# Sample_wiring.net
KiCad netlist of a schematic drawn in EAGLE
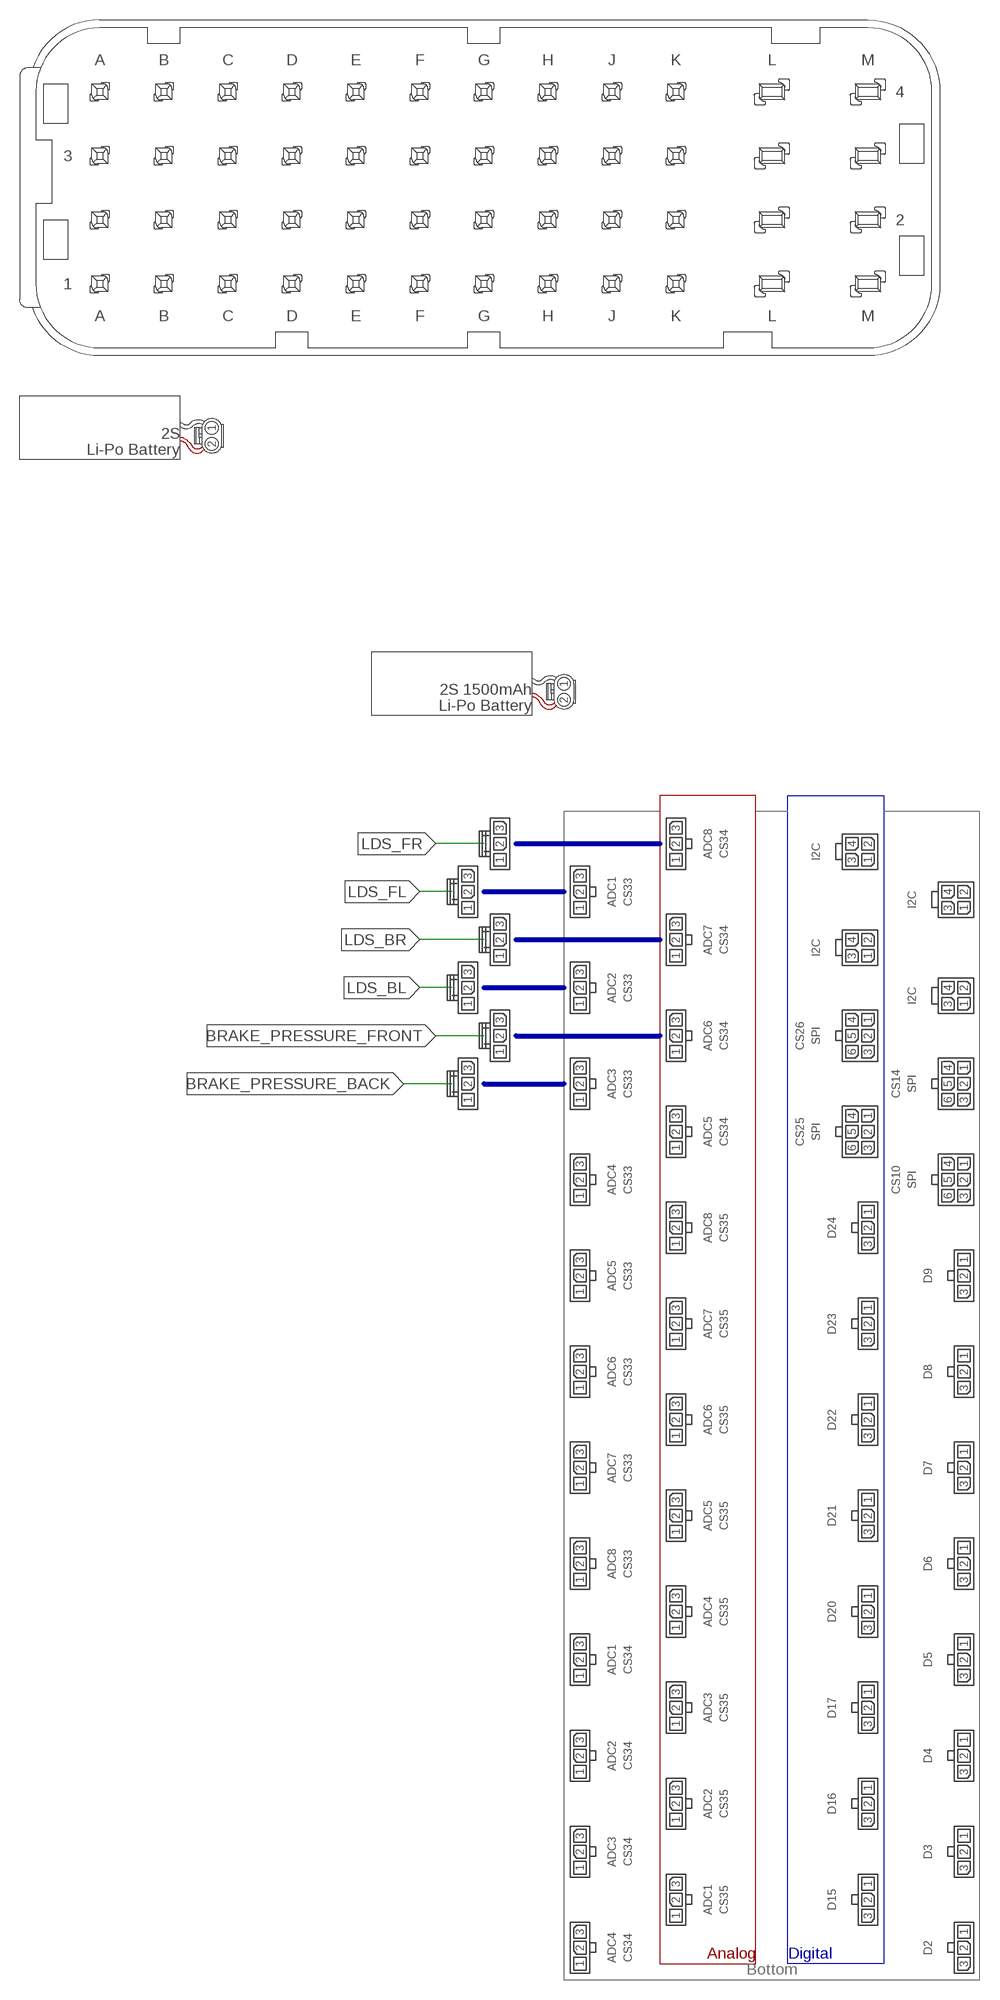
[diagram p0: schematic, sheet 1, part 1 of 2]
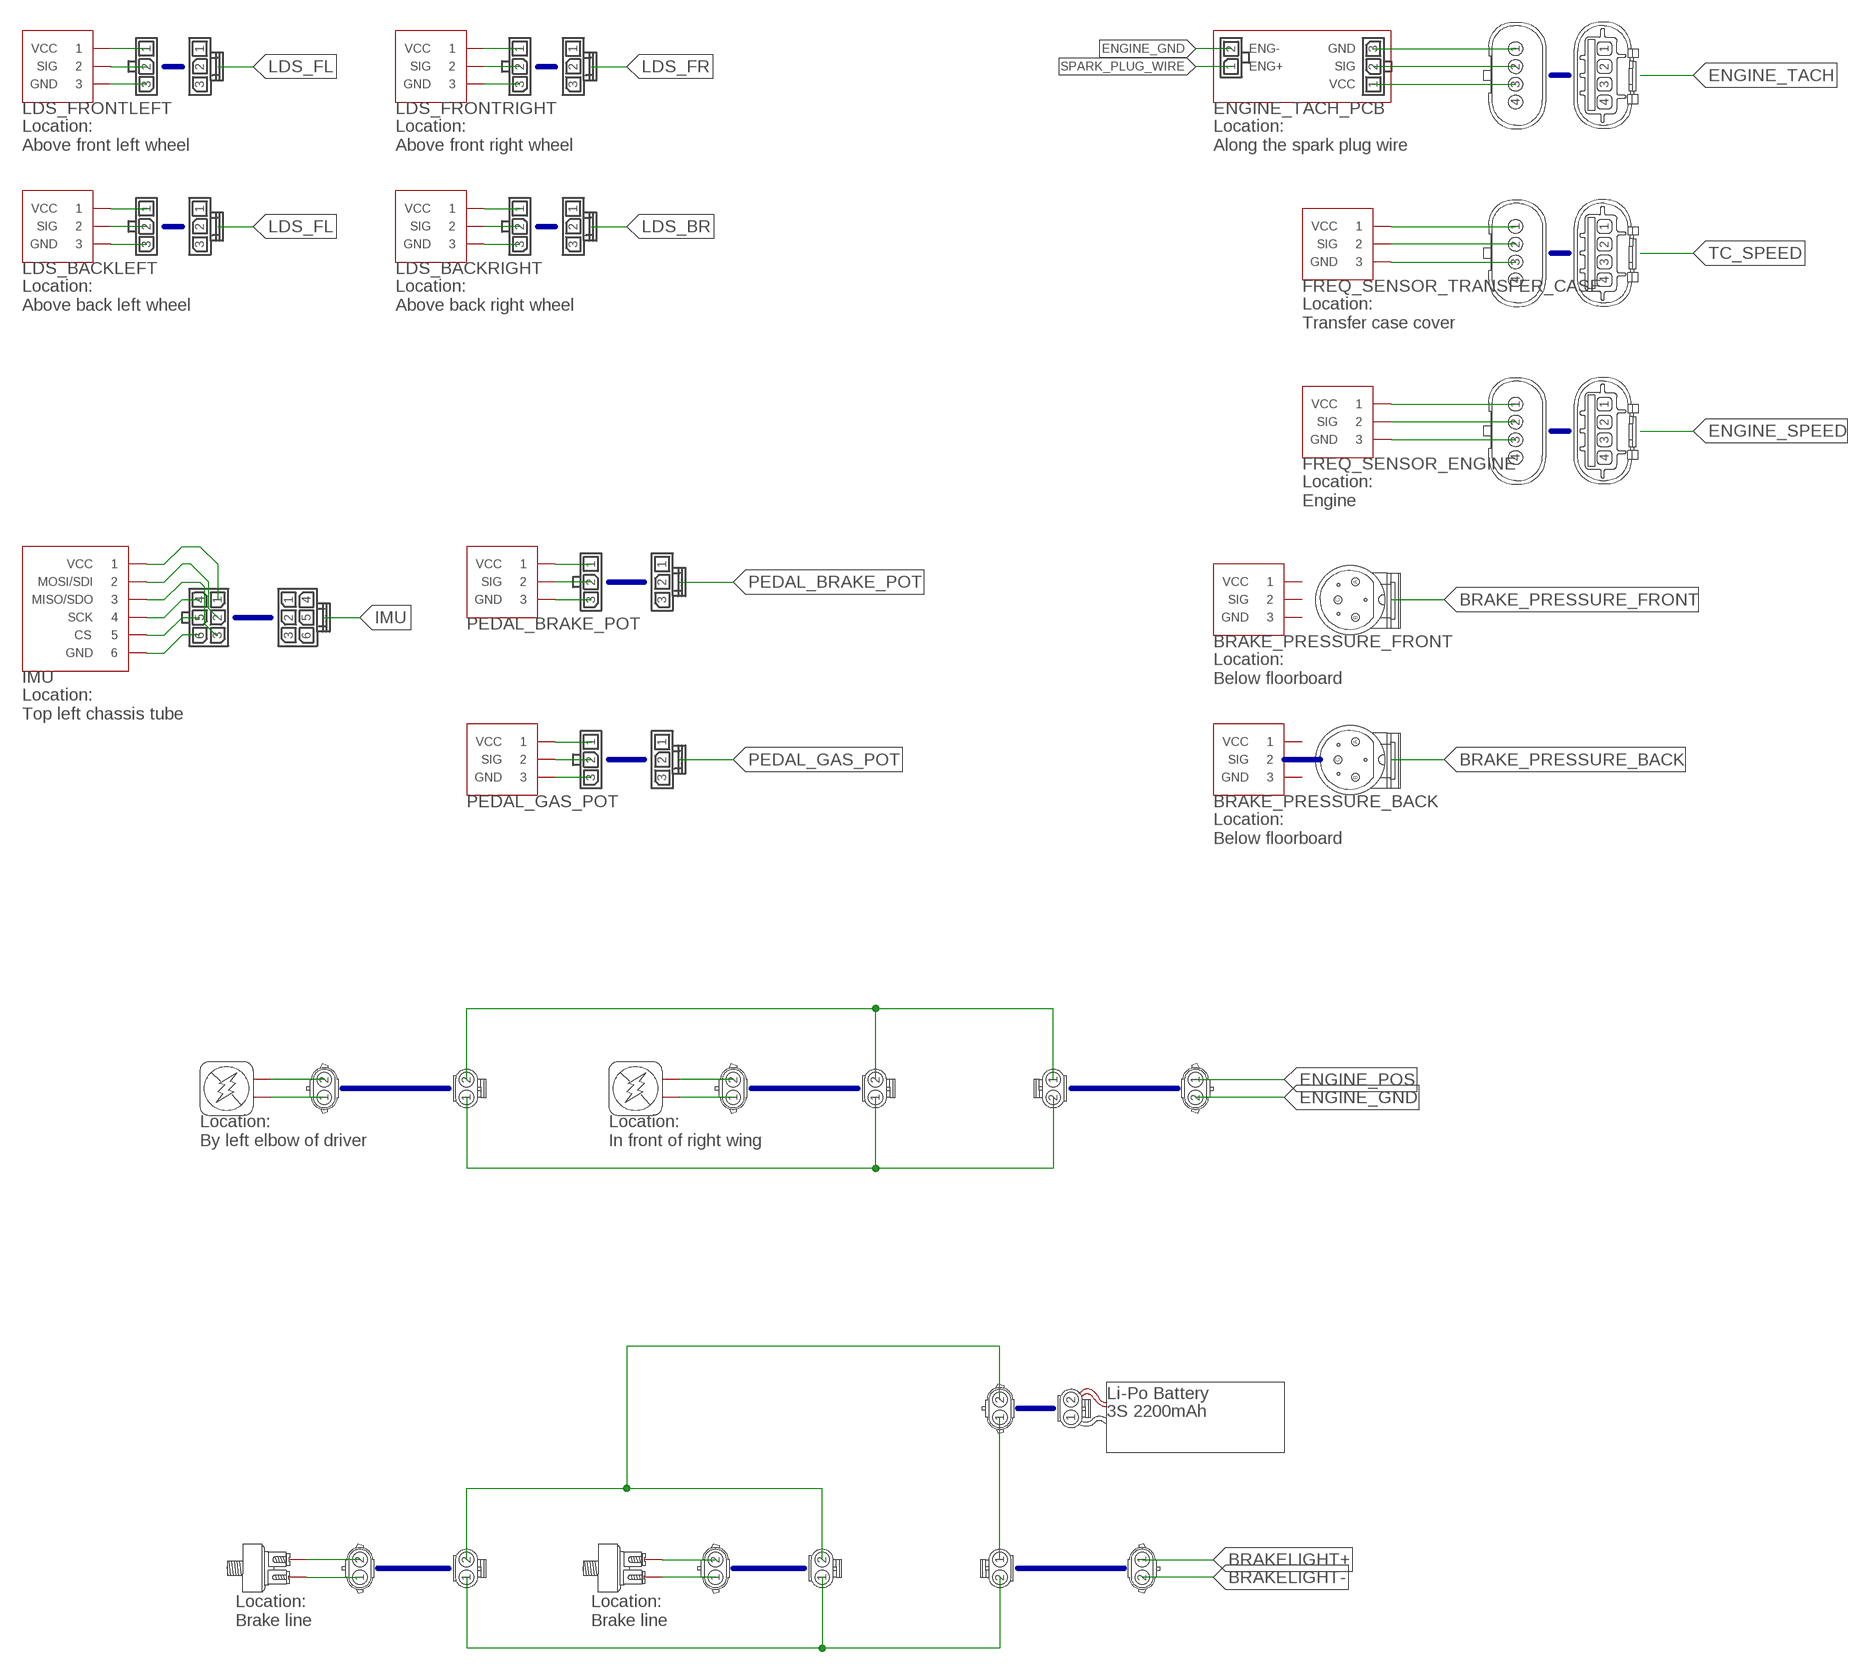
[diagram p1: schematic, sheet 1, part 2 of 2]

(export (version "E")
  (design (tool "Eeschema 10.0.6"))
  (components
    (comp (ref "BRAKE_PRESSURE_BACK")
      (value "SENSOR_1X3")
      (footprint "eagle-import:PINS_3")
      (libsource (lib "eagle-import") (part "SENSOR_1X3"))
    )
    (comp (ref "BRAKE_PRESSURE_FRONT")
      (value "SENSOR_1X3")
      (footprint "eagle-import:PINS_3")
      (libsource (lib "eagle-import") (part "SENSOR_1X3"))
    )
    (comp (ref "ENGINE_TACH_PCB")
      (value "ENGINE_TACH_PCB")
      (footprint "eagle-import:PINS_7")
      (libsource (lib "eagle-import") (part "ENGINE_TACH_PCB"))
    )
    (comp (ref "FREQ_SENSOR_ENGINE")
      (value "SENSOR_1X3")
      (footprint "eagle-import:PINS_3")
      (libsource (lib "eagle-import") (part "SENSOR_1X3"))
    )
    (comp (ref "FREQ_SENSOR_TRANSFER_CASE")
      (value "SENSOR_1X3")
      (footprint "eagle-import:PINS_3")
      (libsource (lib "eagle-import") (part "SENSOR_1X3"))
    )
    (comp (ref "IMU")
      (value "SENSOR_SPI_2X3")
      (footprint "eagle-import:PINS_7")
      (libsource (lib "eagle-import") (part "SENSOR_SPI_2X3"))
    )
    (comp (ref "LDS_BACKLEFT")
      (value "SENSOR_1X3")
      (footprint "eagle-import:PINS_3")
      (libsource (lib "eagle-import") (part "SENSOR_1X3"))
    )
    (comp (ref "LDS_BACKRIGHT")
      (value "SENSOR_1X3")
      (footprint "eagle-import:PINS_3")
      (libsource (lib "eagle-import") (part "SENSOR_1X3"))
    )
    (comp (ref "LDS_FRONTLEFT")
      (value "SENSOR_1X3")
      (footprint "eagle-import:PINS_3")
      (libsource (lib "eagle-import") (part "SENSOR_1X3"))
    )
    (comp (ref "LDS_FRONTRIGHT")
      (value "SENSOR_1X3")
      (footprint "eagle-import:PINS_3")
      (libsource (lib "eagle-import") (part "SENSOR_1X3"))
    )
    (comp (ref "PEDAL_BRAKE_POT")
      (value "SENSOR_1X3")
      (footprint "eagle-import:PINS_3")
      (libsource (lib "eagle-import") (part "SENSOR_1X3"))
    )
    (comp (ref "PEDAL_GAS_POT")
      (value "SENSOR_1X3")
      (footprint "eagle-import:PINS_3")
      (libsource (lib "eagle-import") (part "SENSOR_1X3"))
    )
    (comp (ref "U$1")
      (value "MICROFIT_1X3_MALE")
      (footprint "eagle-import:PINS_4")
      (libsource (lib "eagle-import") (part "MICROFIT_1X3_MALE"))
    )
    (comp (ref "U$2")
      (value "CMC_48PIN_PLUG_PCB")
      (footprint "eagle-import:PINS_49")
      (libsource (lib "eagle-import") (part "CMC_48PIN_PLUG_PCB"))
    )
    (comp (ref "U$3")
      (value "AUXDAQ_REV2")
      (footprint "eagle-import:PINS_200")
      (libsource (lib "eagle-import") (part "AUXDAQ_REV2"))
    )
    (comp (ref "U$4")
      (value "SKIDOO_KILLSWITCH")
      (footprint "eagle-import:PINS_3")
      (libsource (lib "eagle-import") (part "SKIDOO_KILLSWITCH"))
    )
    (comp (ref "U$5")
      (value "WEATHERPACK_1X2_MALE")
      (footprint "eagle-import:PINS_3")
      (libsource (lib "eagle-import") (part "WEATHERPACK_1X2_MALE"))
    )
    (comp (ref "U$6")
      (value "WEATHERPACK_1X2_FEMALE")
      (footprint "eagle-import:PINS_3")
      (libsource (lib "eagle-import") (part "WEATHERPACK_1X2_FEMALE"))
    )
    (comp (ref "U$7")
      (value "WEATHERPACK_1X2_MALE")
      (footprint "eagle-import:PINS_3")
      (libsource (lib "eagle-import") (part "WEATHERPACK_1X2_MALE"))
    )
    (comp (ref "U$8")
      (value "WEATHERPACK_1X2_MALE")
      (footprint "eagle-import:PINS_3")
      (libsource (lib "eagle-import") (part "WEATHERPACK_1X2_MALE"))
    )
    (comp (ref "U$9")
      (value "SKIDOO_KILLSWITCH")
      (footprint "eagle-import:PINS_3")
      (libsource (lib "eagle-import") (part "SKIDOO_KILLSWITCH"))
    )
    (comp (ref "U$10")
      (value "WEATHERPACK_1X2_FEMALE")
      (footprint "eagle-import:PINS_3")
      (libsource (lib "eagle-import") (part "WEATHERPACK_1X2_FEMALE"))
    )
    (comp (ref "U$11")
      (value "WEATHERPACK_1X2_FEMALE")
      (footprint "eagle-import:PINS_3")
      (libsource (lib "eagle-import") (part "WEATHERPACK_1X2_FEMALE"))
    )
    (comp (ref "U$12")
      (value "BRAKELIGHT_SWITCH_HYDRAULIC")
      (footprint "eagle-import:PINS_3")
      (libsource (lib "eagle-import") (part "BRAKELIGHT_SWITCH_HYDRAULIC"))
    )
    (comp (ref "U$13")
      (value "WEATHERPACK_1X2_MALE")
      (footprint "eagle-import:PINS_3")
      (libsource (lib "eagle-import") (part "WEATHERPACK_1X2_MALE"))
    )
    (comp (ref "U$14")
      (value "MICROFIT_1X3_MALE")
      (footprint "eagle-import:PINS_4")
      (libsource (lib "eagle-import") (part "MICROFIT_1X3_MALE"))
    )
    (comp (ref "U$15")
      (value "WEATHERPACK_1X2_FEMALE")
      (footprint "eagle-import:PINS_3")
      (libsource (lib "eagle-import") (part "WEATHERPACK_1X2_FEMALE"))
    )
    (comp (ref "U$16")
      (value "WEATHERPACK_1X2_MALE")
      (footprint "eagle-import:PINS_3")
      (libsource (lib "eagle-import") (part "WEATHERPACK_1X2_MALE"))
    )
    (comp (ref "U$17")
      (value "WEATHERPACK_1X2_MALE")
      (footprint "eagle-import:PINS_3")
      (libsource (lib "eagle-import") (part "WEATHERPACK_1X2_MALE"))
    )
    (comp (ref "U$18")
      (value "BRAKELIGHT_SWITCH_HYDRAULIC")
      (footprint "eagle-import:PINS_3")
      (libsource (lib "eagle-import") (part "BRAKELIGHT_SWITCH_HYDRAULIC"))
    )
    (comp (ref "U$19")
      (value "WEATHERPACK_1X2_FEMALE")
      (footprint "eagle-import:PINS_3")
      (libsource (lib "eagle-import") (part "WEATHERPACK_1X2_FEMALE"))
    )
    (comp (ref "U$20")
      (value "WEATHERPACK_1X2_FEMALE")
      (footprint "eagle-import:PINS_3")
      (libsource (lib "eagle-import") (part "WEATHERPACK_1X2_FEMALE"))
    )
    (comp (ref "U$21")
      (value "MICROFIT_1X3_MALE")
      (footprint "eagle-import:PINS_4")
      (libsource (lib "eagle-import") (part "MICROFIT_1X3_MALE"))
    )
    (comp (ref "U$22")
      (value "MICROFIT_1X3_MALE")
      (footprint "eagle-import:PINS_4")
      (libsource (lib "eagle-import") (part "MICROFIT_1X3_MALE"))
    )
    (comp (ref "U$23")
      (value "MICROFIT_2X3_MALE")
      (footprint "eagle-import:PINS_7")
      (libsource (lib "eagle-import") (part "MICROFIT_2X3_MALE"))
    )
    (comp (ref "U$24")
      (value "MICROFIT_1X3_MALE")
      (footprint "eagle-import:PINS_4")
      (libsource (lib "eagle-import") (part "MICROFIT_1X3_MALE"))
    )
    (comp (ref "U$25")
      (value "MICROFIT_1X3_MALE")
      (footprint "eagle-import:PINS_4")
      (libsource (lib "eagle-import") (part "MICROFIT_1X3_MALE"))
    )
    (comp (ref "U$26")
      (value "SQUBA_1X4_MALE")
      (footprint "eagle-import:PINS_5")
      (libsource (lib "eagle-import") (part "SQUBA_1X4_MALE"))
    )
    (comp (ref "U$27")
      (value "SQUBA_1X4_MALE")
      (footprint "eagle-import:PINS_5")
      (libsource (lib "eagle-import") (part "SQUBA_1X4_MALE"))
    )
    (comp (ref "U$28")
      (value "SQUBA_1X4_MALE")
      (footprint "eagle-import:PINS_5")
      (libsource (lib "eagle-import") (part "SQUBA_1X4_MALE"))
    )
    (comp (ref "U$29")
      (value "3S 2200mAh")
      (footprint "eagle-import:PINS_200")
      (libsource (lib "eagle-import") (part "LIPO_BATT"))
    )
    (comp (ref "U$30")
      (value "2S 1500mAh")
      (footprint "eagle-import:PINS_200")
      (libsource (lib "eagle-import") (part "LIPO_BATT"))
    )
    (comp (ref "U$31")
      (value "2S")
      (footprint "eagle-import:PINS_200")
      (libsource (lib "eagle-import") (part "LIPO_BATT"))
    )
    (comp (ref "U$32")
      (value "WEATHERPACK_1X2_MALE")
      (footprint "eagle-import:PINS_3")
      (libsource (lib "eagle-import") (part "WEATHERPACK_1X2_MALE"))
    )
    (comp (ref "U$33")
      (value "MICROFIT_2X3_FEMALE")
      (footprint "eagle-import:PINS_7")
      (libsource (lib "eagle-import") (part "MICROFIT_2X3_FEMALE"))
    )
    (comp (ref "U$34")
      (value "SQUBA_1X4_FEMALE")
      (footprint "eagle-import:PINS_5")
      (libsource (lib "eagle-import") (part "SQUBA_1X4_FEMALE"))
    )
    (comp (ref "U$35")
      (value "SQUBA_1X4_FEMALE")
      (footprint "eagle-import:PINS_5")
      (libsource (lib "eagle-import") (part "SQUBA_1X4_FEMALE"))
    )
    (comp (ref "U$36")
      (value "SQUBA_1X4_FEMALE")
      (footprint "eagle-import:PINS_5")
      (libsource (lib "eagle-import") (part "SQUBA_1X4_FEMALE"))
    )
    (comp (ref "U$37")
      (value "MICROFIT_1X3_FEMALE")
      (footprint "eagle-import:PINS_4")
      (libsource (lib "eagle-import") (part "MICROFIT_1X3_FEMALE"))
    )
    (comp (ref "U$38")
      (value "MICROFIT_1X3_FEMALE")
      (footprint "eagle-import:PINS_4")
      (libsource (lib "eagle-import") (part "MICROFIT_1X3_FEMALE"))
    )
    (comp (ref "U$39")
      (value "MICROFIT_1X3_FEMALE")
      (footprint "eagle-import:PINS_4")
      (libsource (lib "eagle-import") (part "MICROFIT_1X3_FEMALE"))
    )
    (comp (ref "U$40")
      (value "MICROFIT_1X3_FEMALE")
      (footprint "eagle-import:PINS_4")
      (libsource (lib "eagle-import") (part "MICROFIT_1X3_FEMALE"))
    )
    (comp (ref "U$41")
      (value "MICROFIT_1X3_FEMALE")
      (footprint "eagle-import:PINS_4")
      (libsource (lib "eagle-import") (part "MICROFIT_1X3_FEMALE"))
    )
    (comp (ref "U$42")
      (value "MICROFIT_1X3_FEMALE")
      (footprint "eagle-import:PINS_4")
      (libsource (lib "eagle-import") (part "MICROFIT_1X3_FEMALE"))
    )
    (comp (ref "U$43")
      (value "MICROFIT_1X3_FEMALE")
      (footprint "eagle-import:PINS_4")
      (libsource (lib "eagle-import") (part "MICROFIT_1X3_FEMALE"))
    )
    (comp (ref "U$44")
      (value "MICROFIT_1X3_FEMALE")
      (footprint "eagle-import:PINS_4")
      (libsource (lib "eagle-import") (part "MICROFIT_1X3_FEMALE"))
    )
    (comp (ref "U$45")
      (value "MICROFIT_1X3_FEMALE")
      (footprint "eagle-import:PINS_4")
      (libsource (lib "eagle-import") (part "MICROFIT_1X3_FEMALE"))
    )
    (comp (ref "U$46")
      (value "MICROFIT_1X3_FEMALE")
      (footprint "eagle-import:PINS_4")
      (libsource (lib "eagle-import") (part "MICROFIT_1X3_FEMALE"))
    )
    (comp (ref "U$47")
      (value "METRIPACK_3PIN_FEMALE")
      (footprint "eagle-import:PINS_3")
      (libsource (lib "eagle-import") (part "METRIPACK_3PIN_FEMALE"))
    )
    (comp (ref "U$48")
      (value "METRIPACK_3PIN_FEMALE")
      (footprint "eagle-import:PINS_3")
      (libsource (lib "eagle-import") (part "METRIPACK_3PIN_FEMALE"))
    )
    (comp (ref "U$49")
      (value "MICROFIT_1X3_FEMALE")
      (footprint "eagle-import:PINS_4")
      (libsource (lib "eagle-import") (part "MICROFIT_1X3_FEMALE"))
    )
    (comp (ref "U$50")
      (value "MICROFIT_1X3_FEMALE")
      (footprint "eagle-import:PINS_4")
      (libsource (lib "eagle-import") (part "MICROFIT_1X3_FEMALE"))
    )
  )
  (nets
    (net (code "1") (name "/B$1") (class "Default")
      (node (ref "IMU") (pin "P$1") (pinfunction "1_P$1") (pintype "bidirectional"))
      (node (ref "IMU") (pin "P$2") (pinfunction "2_P$2") (pintype "bidirectional"))
      (node (ref "IMU") (pin "P$3") (pinfunction "3_P$3") (pintype "bidirectional"))
      (node (ref "IMU") (pin "P$4") (pinfunction "4_P$4") (pintype "bidirectional"))
      (node (ref "IMU") (pin "P$5") (pinfunction "5_P$5") (pintype "bidirectional"))
      (node (ref "IMU") (pin "P$6") (pinfunction "6_P$6") (pintype "bidirectional"))
      (node (ref "U$23") (pin "P$1") (pinfunction "1_P$1") (pintype "bidirectional"))
      (node (ref "U$23") (pin "P$2") (pinfunction "2_P$2") (pintype "bidirectional"))
      (node (ref "U$23") (pin "P$3") (pinfunction "3_P$3") (pintype "bidirectional"))
      (node (ref "U$23") (pin "P$4") (pinfunction "4_P$4") (pintype "bidirectional"))
      (node (ref "U$23") (pin "P$5") (pinfunction "5_P$5") (pintype "bidirectional"))
      (node (ref "U$23") (pin "P$6") (pinfunction "6_P$6") (pintype "bidirectional"))
    )
    (net (code "2") (name "/L1") (class "Default")
      (node (ref "U$2") (pin "P$41") (pinfunction "L1_P$41") (pintype "power_in"))
    )
    (net (code "3") (name "/L2") (class "Default")
      (node (ref "U$2") (pin "P$42") (pinfunction "L2_P$42") (pintype "power_in"))
    )
    (net (code "4") (name "/L3") (class "Default")
      (node (ref "U$2") (pin "P$43") (pinfunction "L3_P$43") (pintype "power_in"))
    )
    (net (code "5") (name "/L4") (class "Default")
      (node (ref "U$2") (pin "P$44") (pinfunction "L4_P$44") (pintype "power_in"))
    )
    (net (code "6") (name "/M1") (class "Default")
      (node (ref "U$2") (pin "P$45") (pinfunction "M1_P$45") (pintype "power_in"))
    )
    (net (code "7") (name "/M2") (class "Default")
      (node (ref "U$2") (pin "P$46") (pinfunction "M2_P$46") (pintype "power_in"))
    )
    (net (code "8") (name "/M3") (class "Default")
      (node (ref "U$2") (pin "P$47") (pinfunction "M3_P$47") (pintype "power_in"))
    )
    (net (code "9") (name "/M4") (class "Default")
      (node (ref "U$2") (pin "P$48") (pinfunction "M4_P$48") (pintype "power_in"))
    )
    (net (code "10") (name "BRAKELIGHT+") (class "Default")
      (node (ref "U$16") (pin "P$2") (pinfunction "2_P$2") (pintype "bidirectional"))
    )
    (net (code "11") (name "BRAKELIGHT-") (class "Default")
      (node (ref "U$16") (pin "P$1") (pinfunction "1_P$1") (pintype "bidirectional"))
    )
    (net (code "14") (name "ENGINE_GND") (class "Default")
      (node (ref "ENGINE_TACH_PCB") (pin "P$2") (pinfunction "2_P$2") (pintype "bidirectional"))
      (node (ref "U$7") (pin "P$1") (pinfunction "1_P$1") (pintype "bidirectional"))
    )
    (net (code "15") (name "ENGINE_POS") (class "Default")
      (node (ref "U$7") (pin "P$2") (pinfunction "2_P$2") (pintype "bidirectional"))
    )
    (net (code "23") (name "Net-(ENGINE_TACH_PCB-6)") (class "Default")
      (node (ref "ENGINE_TACH_PCB") (pin "P$3") (pinfunction "6_P$3") (pintype "bidirectional"))
      (node (ref "U$26") (pin "P$3") (pinfunction "3_P$3") (pintype "bidirectional"))
    )
    (net (code "24") (name "Net-(ENGINE_TACH_PCB-7)") (class "Default")
      (node (ref "ENGINE_TACH_PCB") (pin "P$4") (pinfunction "7_P$4") (pintype "bidirectional"))
      (node (ref "U$26") (pin "P$2") (pinfunction "2_P$2") (pintype "bidirectional"))
    )
    (net (code "25") (name "Net-(ENGINE_TACH_PCB-8)") (class "Default")
      (node (ref "ENGINE_TACH_PCB") (pin "P$5") (pinfunction "8_P$5") (pintype "bidirectional"))
      (node (ref "U$26") (pin "P$1") (pinfunction "1_P$1") (pintype "bidirectional"))
    )
    (net (code "26") (name "Net-(FREQ_SENSOR_ENGINE-1)") (class "Default")
      (node (ref "FREQ_SENSOR_ENGINE") (pin "P$1") (pinfunction "1_P$1") (pintype "bidirectional"))
      (node (ref "U$27") (pin "P$1") (pinfunction "1_P$1") (pintype "bidirectional"))
    )
    (net (code "27") (name "Net-(FREQ_SENSOR_ENGINE-2)") (class "Default")
      (node (ref "FREQ_SENSOR_ENGINE") (pin "P$2") (pinfunction "2_P$2") (pintype "bidirectional"))
      (node (ref "U$27") (pin "P$2") (pinfunction "2_P$2") (pintype "bidirectional"))
    )
    (net (code "28") (name "Net-(FREQ_SENSOR_ENGINE-3)") (class "Default")
      (node (ref "FREQ_SENSOR_ENGINE") (pin "P$3") (pinfunction "3_P$3") (pintype "bidirectional"))
      (node (ref "U$27") (pin "P$3") (pinfunction "3_P$3") (pintype "bidirectional"))
    )
    (net (code "29") (name "Net-(FREQ_SENSOR_TRANSFER_CASE-1)") (class "Default")
      (node (ref "FREQ_SENSOR_TRANSFER_CASE") (pin "P$1") (pinfunction "1_P$1") (pintype "bidirectional"))
      (node (ref "U$28") (pin "P$1") (pinfunction "1_P$1") (pintype "bidirectional"))
    )
    (net (code "30") (name "Net-(FREQ_SENSOR_TRANSFER_CASE-2)") (class "Default")
      (node (ref "FREQ_SENSOR_TRANSFER_CASE") (pin "P$2") (pinfunction "2_P$2") (pintype "bidirectional"))
      (node (ref "U$28") (pin "P$2") (pinfunction "2_P$2") (pintype "bidirectional"))
    )
    (net (code "31") (name "Net-(FREQ_SENSOR_TRANSFER_CASE-3)") (class "Default")
      (node (ref "FREQ_SENSOR_TRANSFER_CASE") (pin "P$3") (pinfunction "3_P$3") (pintype "bidirectional"))
      (node (ref "U$28") (pin "P$3") (pinfunction "3_P$3") (pintype "bidirectional"))
    )
    (net (code "32") (name "Net-(LDS_BACKLEFT-1)") (class "Default")
      (node (ref "LDS_BACKLEFT") (pin "P$1") (pinfunction "1_P$1") (pintype "bidirectional"))
      (node (ref "U$14") (pin "P$1") (pinfunction "1_P$1") (pintype "bidirectional"))
    )
    (net (code "33") (name "Net-(LDS_BACKLEFT-2)") (class "Default")
      (node (ref "LDS_BACKLEFT") (pin "P$2") (pinfunction "2_P$2") (pintype "bidirectional"))
      (node (ref "U$14") (pin "P$2") (pinfunction "2_P$2") (pintype "bidirectional"))
    )
    (net (code "34") (name "Net-(LDS_BACKLEFT-3)") (class "Default")
      (node (ref "LDS_BACKLEFT") (pin "P$3") (pinfunction "3_P$3") (pintype "bidirectional"))
      (node (ref "U$14") (pin "P$3") (pinfunction "3_P$3") (pintype "bidirectional"))
    )
    (net (code "35") (name "Net-(LDS_BACKRIGHT-1)") (class "Default")
      (node (ref "LDS_BACKRIGHT") (pin "P$1") (pinfunction "1_P$1") (pintype "bidirectional"))
      (node (ref "U$22") (pin "P$1") (pinfunction "1_P$1") (pintype "bidirectional"))
    )
    (net (code "36") (name "Net-(LDS_BACKRIGHT-2)") (class "Default")
      (node (ref "LDS_BACKRIGHT") (pin "P$2") (pinfunction "2_P$2") (pintype "bidirectional"))
      (node (ref "U$22") (pin "P$2") (pinfunction "2_P$2") (pintype "bidirectional"))
    )
    (net (code "37") (name "Net-(LDS_BACKRIGHT-3)") (class "Default")
      (node (ref "LDS_BACKRIGHT") (pin "P$3") (pinfunction "3_P$3") (pintype "bidirectional"))
      (node (ref "U$22") (pin "P$3") (pinfunction "3_P$3") (pintype "bidirectional"))
    )
    (net (code "38") (name "Net-(LDS_FRONTLEFT-1)") (class "Default")
      (node (ref "LDS_FRONTLEFT") (pin "P$1") (pinfunction "1_P$1") (pintype "bidirectional"))
      (node (ref "U$1") (pin "P$1") (pinfunction "1_P$1") (pintype "bidirectional"))
    )
    (net (code "39") (name "Net-(LDS_FRONTLEFT-2)") (class "Default")
      (node (ref "LDS_FRONTLEFT") (pin "P$2") (pinfunction "2_P$2") (pintype "bidirectional"))
      (node (ref "U$1") (pin "P$2") (pinfunction "2_P$2") (pintype "bidirectional"))
    )
    (net (code "40") (name "Net-(LDS_FRONTLEFT-3)") (class "Default")
      (node (ref "LDS_FRONTLEFT") (pin "P$3") (pinfunction "3_P$3") (pintype "bidirectional"))
      (node (ref "U$1") (pin "P$3") (pinfunction "3_P$3") (pintype "bidirectional"))
    )
    (net (code "41") (name "Net-(LDS_FRONTRIGHT-1)") (class "Default")
      (node (ref "LDS_FRONTRIGHT") (pin "P$1") (pinfunction "1_P$1") (pintype "bidirectional"))
      (node (ref "U$21") (pin "P$1") (pinfunction "1_P$1") (pintype "bidirectional"))
    )
    (net (code "42") (name "Net-(LDS_FRONTRIGHT-2)") (class "Default")
      (node (ref "LDS_FRONTRIGHT") (pin "P$2") (pinfunction "2_P$2") (pintype "bidirectional"))
      (node (ref "U$21") (pin "P$2") (pinfunction "2_P$2") (pintype "bidirectional"))
    )
    (net (code "43") (name "Net-(LDS_FRONTRIGHT-3)") (class "Default")
      (node (ref "LDS_FRONTRIGHT") (pin "P$3") (pinfunction "3_P$3") (pintype "bidirectional"))
      (node (ref "U$21") (pin "P$3") (pinfunction "3_P$3") (pintype "bidirectional"))
    )
    (net (code "44") (name "Net-(PEDAL_BRAKE_POT-1)") (class "Default")
      (node (ref "PEDAL_BRAKE_POT") (pin "P$1") (pinfunction "1_P$1") (pintype "bidirectional"))
      (node (ref "U$24") (pin "P$1") (pinfunction "1_P$1") (pintype "bidirectional"))
    )
    (net (code "45") (name "Net-(PEDAL_BRAKE_POT-2)") (class "Default")
      (node (ref "PEDAL_BRAKE_POT") (pin "P$2") (pinfunction "2_P$2") (pintype "bidirectional"))
      (node (ref "U$24") (pin "P$2") (pinfunction "2_P$2") (pintype "bidirectional"))
    )
    (net (code "46") (name "Net-(PEDAL_BRAKE_POT-3)") (class "Default")
      (node (ref "PEDAL_BRAKE_POT") (pin "P$3") (pinfunction "3_P$3") (pintype "bidirectional"))
      (node (ref "U$24") (pin "P$3") (pinfunction "3_P$3") (pintype "bidirectional"))
    )
    (net (code "47") (name "Net-(PEDAL_GAS_POT-1)") (class "Default")
      (node (ref "PEDAL_GAS_POT") (pin "P$1") (pinfunction "1_P$1") (pintype "bidirectional"))
      (node (ref "U$25") (pin "P$1") (pinfunction "1_P$1") (pintype "bidirectional"))
    )
    (net (code "48") (name "Net-(PEDAL_GAS_POT-2)") (class "Default")
      (node (ref "PEDAL_GAS_POT") (pin "P$2") (pinfunction "2_P$2") (pintype "bidirectional"))
      (node (ref "U$25") (pin "P$2") (pinfunction "2_P$2") (pintype "bidirectional"))
    )
    (net (code "49") (name "Net-(PEDAL_GAS_POT-3)") (class "Default")
      (node (ref "PEDAL_GAS_POT") (pin "P$3") (pinfunction "3_P$3") (pintype "bidirectional"))
      (node (ref "U$25") (pin "P$3") (pinfunction "3_P$3") (pintype "bidirectional"))
    )
    (net (code "50") (name "Net-(U$5-1)") (class "Default")
      (node (ref "U$4") (pin "P$2") (pinfunction "P$2_P$2") (pintype "bidirectional"))
      (node (ref "U$5") (pin "P$1") (pinfunction "1_P$1") (pintype "bidirectional"))
    )
    (net (code "51") (name "Net-(U$5-2)") (class "Default")
      (node (ref "U$4") (pin "P$1") (pinfunction "P$1_P$1") (pintype "bidirectional"))
      (node (ref "U$5") (pin "P$2") (pinfunction "2_P$2") (pintype "bidirectional"))
    )
    (net (code "52") (name "Net-(U$8-1)") (class "Default")
      (node (ref "U$8") (pin "P$1") (pinfunction "1_P$1") (pintype "bidirectional"))
      (node (ref "U$9") (pin "P$2") (pinfunction "P$2_P$2") (pintype "bidirectional"))
    )
    (net (code "53") (name "Net-(U$8-2)") (class "Default")
      (node (ref "U$8") (pin "P$2") (pinfunction "2_P$2") (pintype "bidirectional"))
      (node (ref "U$9") (pin "P$1") (pinfunction "P$1_P$1") (pintype "bidirectional"))
    )
    (net (code "54") (name "Net-(U$10-1)") (class "Default")
      (node (ref "U$10") (pin "P$1") (pinfunction "1_P$1") (pintype "bidirectional"))
      (node (ref "U$11") (pin "P$2") (pinfunction "2_P$2") (pintype "bidirectional"))
      (node (ref "U$6") (pin "P$1") (pinfunction "1_P$1") (pintype "bidirectional"))
    )
    (net (code "55") (name "Net-(U$10-2)") (class "Default")
      (node (ref "U$10") (pin "P$2") (pinfunction "2_P$2") (pintype "bidirectional"))
      (node (ref "U$11") (pin "P$1") (pinfunction "1_P$1") (pintype "bidirectional"))
      (node (ref "U$6") (pin "P$2") (pinfunction "2_P$2") (pintype "bidirectional"))
    )
    (net (code "56") (name "Net-(U$13-1)") (class "Default")
      (node (ref "U$13") (pin "P$1") (pinfunction "1_P$1") (pintype "bidirectional"))
      (node (ref "U$18") (pin "P$1") (pinfunction "P$1_P$1") (pintype "bidirectional"))
    )
    (net (code "57") (name "Net-(U$13-2)") (class "Default")
      (node (ref "U$13") (pin "P$2") (pinfunction "2_P$2") (pintype "bidirectional"))
      (node (ref "U$18") (pin "P$2") (pinfunction "P$2_P$2") (pintype "bidirectional"))
    )
    (net (code "58") (name "Net-(U$15-1)") (class "Default")
      (node (ref "U$15") (pin "P$1") (pinfunction "1_P$1") (pintype "bidirectional"))
      (node (ref "U$19") (pin "P$1") (pinfunction "1_P$1") (pintype "bidirectional"))
      (node (ref "U$20") (pin "P$2") (pinfunction "2_P$2") (pintype "bidirectional"))
    )
    (net (code "59") (name "Net-(U$15-2)") (class "Default")
      (node (ref "U$15") (pin "P$2") (pinfunction "2_P$2") (pintype "bidirectional"))
      (node (ref "U$19") (pin "P$2") (pinfunction "2_P$2") (pintype "bidirectional"))
      (node (ref "U$32") (pin "P$1") (pinfunction "1_P$1") (pintype "bidirectional"))
    )
    (net (code "60") (name "Net-(U$17-1)") (class "Default")
      (node (ref "U$12") (pin "P$1") (pinfunction "P$1_P$1") (pintype "bidirectional"))
      (node (ref "U$17") (pin "P$1") (pinfunction "1_P$1") (pintype "bidirectional"))
    )
    (net (code "61") (name "Net-(U$17-2)") (class "Default")
      (node (ref "U$12") (pin "P$2") (pinfunction "P$2_P$2") (pintype "bidirectional"))
      (node (ref "U$17") (pin "P$2") (pinfunction "2_P$2") (pintype "bidirectional"))
    )
    (net (code "62") (name "Net-(U$20-1)") (class "Default")
      (node (ref "U$20") (pin "P$1") (pinfunction "1_P$1") (pintype "bidirectional"))
      (node (ref "U$32") (pin "P$2") (pinfunction "2_P$2") (pintype "bidirectional"))
    )
    (net (code "65") (name "SPARK_PLUG_WIRE") (class "Default")
      (node (ref "ENGINE_TACH_PCB") (pin "P$1") (pinfunction "1_P$1") (pintype "bidirectional"))
    )
    (net (code "67") (name "unconnected-(BRAKE_PRESSURE_BACK-1-PadP$1)") (class "Default")
      (node (ref "BRAKE_PRESSURE_BACK") (pin "P$1") (pinfunction "1_P$1") (pintype "bidirectional"))
    )
    (net (code "68") (name "unconnected-(BRAKE_PRESSURE_BACK-2-PadP$2)") (class "Default")
      (node (ref "BRAKE_PRESSURE_BACK") (pin "P$2") (pinfunction "2_P$2") (pintype "bidirectional"))
    )
    (net (code "69") (name "unconnected-(BRAKE_PRESSURE_BACK-3-PadP$3)") (class "Default")
      (node (ref "BRAKE_PRESSURE_BACK") (pin "P$3") (pinfunction "3_P$3") (pintype "bidirectional"))
    )
    (net (code "70") (name "unconnected-(BRAKE_PRESSURE_FRONT-1-PadP$1)") (class "Default")
      (node (ref "BRAKE_PRESSURE_FRONT") (pin "P$1") (pinfunction "1_P$1") (pintype "bidirectional"))
    )
    (net (code "71") (name "unconnected-(BRAKE_PRESSURE_FRONT-2-PadP$2)") (class "Default")
      (node (ref "BRAKE_PRESSURE_FRONT") (pin "P$2") (pinfunction "2_P$2") (pintype "bidirectional"))
    )
    (net (code "72") (name "unconnected-(BRAKE_PRESSURE_FRONT-3-PadP$3)") (class "Default")
      (node (ref "BRAKE_PRESSURE_FRONT") (pin "P$3") (pinfunction "3_P$3") (pintype "bidirectional"))
    )
    (net (code "73") (name "unconnected-(U$2-A1-PadP$1)") (class "Default")
      (node (ref "U$2") (pin "P$1") (pinfunction "A1_P$1") (pintype "bidirectional"))
    )
    (net (code "74") (name "unconnected-(U$2-A2-PadP$2)") (class "Default")
      (node (ref "U$2") (pin "P$2") (pinfunction "A2_P$2") (pintype "bidirectional"))
    )
    (net (code "75") (name "unconnected-(U$2-A3-PadP$3)") (class "Default")
      (node (ref "U$2") (pin "P$3") (pinfunction "A3_P$3") (pintype "bidirectional"))
    )
    (net (code "76") (name "unconnected-(U$2-A4-PadP$4)") (class "Default")
      (node (ref "U$2") (pin "P$4") (pinfunction "A4_P$4") (pintype "bidirectional"))
    )
    (net (code "77") (name "unconnected-(U$2-B1-PadP$5)") (class "Default")
      (node (ref "U$2") (pin "P$5") (pinfunction "B1_P$5") (pintype "bidirectional"))
    )
    (net (code "78") (name "unconnected-(U$2-B2-PadP$6)") (class "Default")
      (node (ref "U$2") (pin "P$6") (pinfunction "B2_P$6") (pintype "bidirectional"))
    )
    (net (code "79") (name "unconnected-(U$2-B3-PadP$7)") (class "Default")
      (node (ref "U$2") (pin "P$7") (pinfunction "B3_P$7") (pintype "bidirectional"))
    )
    (net (code "80") (name "unconnected-(U$2-B4-PadP$8)") (class "Default")
      (node (ref "U$2") (pin "P$8") (pinfunction "B4_P$8") (pintype "bidirectional"))
    )
    (net (code "81") (name "unconnected-(U$2-C1-PadP$9)") (class "Default")
      (node (ref "U$2") (pin "P$9") (pinfunction "C1_P$9") (pintype "bidirectional"))
    )
    (net (code "82") (name "unconnected-(U$2-C2-PadP$10)") (class "Default")
      (node (ref "U$2") (pin "P$10") (pinfunction "C2_P$10") (pintype "bidirectional"))
    )
    (net (code "83") (name "unconnected-(U$2-C3-PadP$11)") (class "Default")
      (node (ref "U$2") (pin "P$11") (pinfunction "C3_P$11") (pintype "bidirectional"))
    )
    (net (code "84") (name "unconnected-(U$2-C4-PadP$12)") (class "Default")
      (node (ref "U$2") (pin "P$12") (pinfunction "C4_P$12") (pintype "bidirectional"))
    )
    (net (code "85") (name "unconnected-(U$2-D1-PadP$13)") (class "Default")
      (node (ref "U$2") (pin "P$13") (pinfunction "D1_P$13") (pintype "bidirectional"))
    )
    (net (code "86") (name "unconnected-(U$2-D2-PadP$14)") (class "Default")
      (node (ref "U$2") (pin "P$14") (pinfunction "D2_P$14") (pintype "bidirectional"))
    )
    (net (code "87") (name "unconnected-(U$2-D3-PadP$15)") (class "Default")
      (node (ref "U$2") (pin "P$15") (pinfunction "D3_P$15") (pintype "bidirectional"))
    )
    (net (code "88") (name "unconnected-(U$2-D4-PadP$16)") (class "Default")
      (node (ref "U$2") (pin "P$16") (pinfunction "D4_P$16") (pintype "bidirectional"))
    )
    (net (code "89") (name "unconnected-(U$2-E1-PadP$17)") (class "Default")
      (node (ref "U$2") (pin "P$17") (pinfunction "E1_P$17") (pintype "bidirectional"))
    )
    (net (code "90") (name "unconnected-(U$2-E2-PadP$18)") (class "Default")
      (node (ref "U$2") (pin "P$18") (pinfunction "E2_P$18") (pintype "bidirectional"))
    )
    (net (code "91") (name "unconnected-(U$2-E3-PadP$19)") (class "Default")
      (node (ref "U$2") (pin "P$19") (pinfunction "E3_P$19") (pintype "bidirectional"))
    )
    (net (code "92") (name "unconnected-(U$2-E4-PadP$20)") (class "Default")
      (node (ref "U$2") (pin "P$20") (pinfunction "E4_P$20") (pintype "bidirectional"))
    )
    (net (code "93") (name "unconnected-(U$2-F1-PadP$21)") (class "Default")
      (node (ref "U$2") (pin "P$21") (pinfunction "F1_P$21") (pintype "bidirectional"))
    )
    (net (code "94") (name "unconnected-(U$2-F2-PadP$22)") (class "Default")
      (node (ref "U$2") (pin "P$22") (pinfunction "F2_P$22") (pintype "bidirectional"))
    )
    (net (code "95") (name "unconnected-(U$2-F3-PadP$23)") (class "Default")
      (node (ref "U$2") (pin "P$23") (pinfunction "F3_P$23") (pintype "bidirectional"))
    )
    (net (code "96") (name "unconnected-(U$2-F4-PadP$24)") (class "Default")
      (node (ref "U$2") (pin "P$24") (pinfunction "F4_P$24") (pintype "bidirectional"))
    )
    (net (code "97") (name "unconnected-(U$2-G1-PadP$25)") (class "Default")
      (node (ref "U$2") (pin "P$25") (pinfunction "G1_P$25") (pintype "bidirectional"))
    )
    (net (code "98") (name "unconnected-(U$2-G2-PadP$26)") (class "Default")
      (node (ref "U$2") (pin "P$26") (pinfunction "G2_P$26") (pintype "bidirectional"))
    )
    (net (code "99") (name "unconnected-(U$2-G3-PadP$27)") (class "Default")
      (node (ref "U$2") (pin "P$27") (pinfunction "G3_P$27") (pintype "bidirectional"))
    )
    (net (code "100") (name "unconnected-(U$2-G4-PadP$28)") (class "Default")
      (node (ref "U$2") (pin "P$28") (pinfunction "G4_P$28") (pintype "bidirectional"))
    )
    (net (code "101") (name "unconnected-(U$2-H1-PadP$29)") (class "Default")
      (node (ref "U$2") (pin "P$29") (pinfunction "H1_P$29") (pintype "bidirectional"))
    )
    (net (code "102") (name "unconnected-(U$2-H2-PadP$30)") (class "Default")
      (node (ref "U$2") (pin "P$30") (pinfunction "H2_P$30") (pintype "bidirectional"))
    )
    (net (code "103") (name "unconnected-(U$2-H3-PadP$31)") (class "Default")
      (node (ref "U$2") (pin "P$31") (pinfunction "H3_P$31") (pintype "bidirectional"))
    )
    (net (code "104") (name "unconnected-(U$2-H4-PadP$32)") (class "Default")
      (node (ref "U$2") (pin "P$32") (pinfunction "H4_P$32") (pintype "bidirectional"))
    )
    (net (code "105") (name "unconnected-(U$2-J1-PadP$33)") (class "Default")
      (node (ref "U$2") (pin "P$33") (pinfunction "J1_P$33") (pintype "bidirectional"))
    )
    (net (code "106") (name "unconnected-(U$2-J2-PadP$34)") (class "Default")
      (node (ref "U$2") (pin "P$34") (pinfunction "J2_P$34") (pintype "bidirectional"))
    )
    (net (code "107") (name "unconnected-(U$2-J3-PadP$35)") (class "Default")
      (node (ref "U$2") (pin "P$35") (pinfunction "J3_P$35") (pintype "bidirectional"))
    )
    (net (code "108") (name "unconnected-(U$2-J4-PadP$36)") (class "Default")
      (node (ref "U$2") (pin "P$36") (pinfunction "J4_P$36") (pintype "bidirectional"))
    )
    (net (code "109") (name "unconnected-(U$2-K1-PadP$37)") (class "Default")
      (node (ref "U$2") (pin "P$37") (pinfunction "K1_P$37") (pintype "bidirectional"))
    )
    (net (code "110") (name "unconnected-(U$2-K2-PadP$38)") (class "Default")
      (node (ref "U$2") (pin "P$38") (pinfunction "K2_P$38") (pintype "bidirectional"))
    )
    (net (code "111") (name "unconnected-(U$2-K3-PadP$39)") (class "Default")
      (node (ref "U$2") (pin "P$39") (pinfunction "K3_P$39") (pintype "bidirectional"))
    )
    (net (code "112") (name "unconnected-(U$2-K4-PadP$40)") (class "Default")
      (node (ref "U$2") (pin "P$40") (pinfunction "K4_P$40") (pintype "bidirectional"))
    )
    (net (code "113") (name "unconnected-(U$3-PadP$1)") (class "Default")
      (node (ref "U$3") (pin "P$1") (pinfunction "P$1_P$1") (pintype "bidirectional"))
    )
    (net (code "114") (name "unconnected-(U$3-PadP$2)") (class "Default")
      (node (ref "U$3") (pin "P$2") (pinfunction "P$2_P$2") (pintype "bidirectional"))
    )
    (net (code "115") (name "unconnected-(U$3-PadP$3)") (class "Default")
      (node (ref "U$3") (pin "P$3") (pinfunction "P$3_P$3") (pintype "bidirectional"))
    )
    (net (code "116") (name "unconnected-(U$3-PadP$4)") (class "Default")
      (node (ref "U$3") (pin "P$4") (pinfunction "P$4_P$4") (pintype "bidirectional"))
    )
    (net (code "117") (name "unconnected-(U$3-PadP$5)") (class "Default")
      (node (ref "U$3") (pin "P$5") (pinfunction "P$5_P$5") (pintype "bidirectional"))
    )
    (net (code "118") (name "unconnected-(U$3-PadP$6)") (class "Default")
      (node (ref "U$3") (pin "P$6") (pinfunction "P$6_P$6") (pintype "bidirectional"))
    )
    (net (code "119") (name "unconnected-(U$3-PadP$7)") (class "Default")
      (node (ref "U$3") (pin "P$7") (pinfunction "P$7_P$7") (pintype "bidirectional"))
    )
    (net (code "120") (name "unconnected-(U$3-PadP$8)") (class "Default")
      (node (ref "U$3") (pin "P$8") (pinfunction "P$8_P$8") (pintype "bidirectional"))
    )
    (net (code "121") (name "unconnected-(U$3-PadP$9)") (class "Default")
      (node (ref "U$3") (pin "P$9") (pinfunction "P$9_P$9") (pintype "bidirectional"))
    )
    (net (code "122") (name "unconnected-(U$3-PadP$10)") (class "Default")
      (node (ref "U$3") (pin "P$10") (pinfunction "P$10_P$10") (pintype "bidirectional"))
    )
    (net (code "123") (name "unconnected-(U$3-PadP$11)") (class "Default")
      (node (ref "U$3") (pin "P$11") (pinfunction "P$11_P$11") (pintype "bidirectional"))
    )
    (net (code "124") (name "unconnected-(U$3-PadP$12)") (class "Default")
      (node (ref "U$3") (pin "P$12") (pinfunction "P$12_P$12") (pintype "bidirectional"))
    )
    (net (code "125") (name "unconnected-(U$3-PadP$13)") (class "Default")
      (node (ref "U$3") (pin "P$13") (pinfunction "P$13_P$13") (pintype "bidirectional"))
    )
    (net (code "126") (name "unconnected-(U$3-PadP$14)") (class "Default")
      (node (ref "U$3") (pin "P$14") (pinfunction "P$14_P$14") (pintype "bidirectional"))
    )
    (net (code "127") (name "unconnected-(U$3-PadP$15)") (class "Default")
      (node (ref "U$3") (pin "P$15") (pinfunction "P$15_P$15") (pintype "bidirectional"))
    )
    (net (code "128") (name "unconnected-(U$3-PadP$16)") (class "Default")
      (node (ref "U$3") (pin "P$16") (pinfunction "P$16_P$16") (pintype "bidirectional"))
    )
    (net (code "129") (name "unconnected-(U$3-PadP$17)") (class "Default")
      (node (ref "U$3") (pin "P$17") (pinfunction "P$17_P$17") (pintype "bidirectional"))
    )
    (net (code "130") (name "unconnected-(U$3-PadP$18)") (class "Default")
      (node (ref "U$3") (pin "P$18") (pinfunction "P$18_P$18") (pintype "bidirectional"))
    )
    (net (code "131") (name "unconnected-(U$3-PadP$19)") (class "Default")
      (node (ref "U$3") (pin "P$19") (pinfunction "P$19_P$19") (pintype "bidirectional"))
    )
    (net (code "132") (name "unconnected-(U$3-PadP$20)") (class "Default")
      (node (ref "U$3") (pin "P$20") (pinfunction "P$20_P$20") (pintype "bidirectional"))
    )
    (net (code "133") (name "unconnected-(U$3-PadP$21)") (class "Default")
      (node (ref "U$3") (pin "P$21") (pinfunction "P$21_P$21") (pintype "bidirectional"))
    )
    (net (code "134") (name "unconnected-(U$3-PadP$22)") (class "Default")
      (node (ref "U$3") (pin "P$22") (pinfunction "P$22_P$22") (pintype "bidirectional"))
    )
    (net (code "135") (name "unconnected-(U$3-PadP$23)") (class "Default")
      (node (ref "U$3") (pin "P$23") (pinfunction "P$23_P$23") (pintype "bidirectional"))
    )
    (net (code "136") (name "unconnected-(U$3-PadP$24)") (class "Default")
      (node (ref "U$3") (pin "P$24") (pinfunction "P$24_P$24") (pintype "bidirectional"))
    )
    (net (code "137") (name "unconnected-(U$3-PadP$25)") (class "Default")
      (node (ref "U$3") (pin "P$25") (pinfunction "P$25_P$25") (pintype "bidirectional"))
    )
    (net (code "138") (name "unconnected-(U$3-PadP$26)") (class "Default")
      (node (ref "U$3") (pin "P$26") (pinfunction "P$26_P$26") (pintype "bidirectional"))
    )
    (net (code "139") (name "unconnected-(U$3-PadP$27)") (class "Default")
      (node (ref "U$3") (pin "P$27") (pinfunction "P$27_P$27") (pintype "bidirectional"))
    )
    (net (code "140") (name "unconnected-(U$3-PadP$28)") (class "Default")
      (node (ref "U$3") (pin "P$28") (pinfunction "P$28_P$28") (pintype "bidirectional"))
    )
    (net (code "141") (name "unconnected-(U$3-PadP$29)") (class "Default")
      (node (ref "U$3") (pin "P$29") (pinfunction "P$29_P$29") (pintype "bidirectional"))
    )
    (net (code "142") (name "unconnected-(U$3-PadP$30)") (class "Default")
      (node (ref "U$3") (pin "P$30") (pinfunction "P$30_P$30") (pintype "bidirectional"))
    )
    (net (code "143") (name "unconnected-(U$3-PadP$31)") (class "Default")
      (node (ref "U$3") (pin "P$31") (pinfunction "P$31_P$31") (pintype "bidirectional"))
    )
    (net (code "144") (name "unconnected-(U$3-PadP$32)") (class "Default")
      (node (ref "U$3") (pin "P$32") (pinfunction "P$32_P$32") (pintype "bidirectional"))
    )
    (net (code "145") (name "unconnected-(U$3-PadP$33)") (class "Default")
      (node (ref "U$3") (pin "P$33") (pinfunction "P$33_P$33") (pintype "bidirectional"))
    )
    (net (code "146") (name "unconnected-(U$3-PadP$34)") (class "Default")
      (node (ref "U$3") (pin "P$34") (pinfunction "P$34_P$34") (pintype "bidirectional"))
    )
    (net (code "147") (name "unconnected-(U$3-PadP$35)") (class "Default")
      (node (ref "U$3") (pin "P$35") (pinfunction "P$35_P$35") (pintype "bidirectional"))
    )
    (net (code "148") (name "unconnected-(U$3-PadP$36)") (class "Default")
      (node (ref "U$3") (pin "P$36") (pinfunction "P$36_P$36") (pintype "bidirectional"))
    )
    (net (code "149") (name "unconnected-(U$3-PadP$37)") (class "Default")
      (node (ref "U$3") (pin "P$37") (pinfunction "P$37_P$37") (pintype "bidirectional"))
    )
    (net (code "150") (name "unconnected-(U$3-PadP$38)") (class "Default")
      (node (ref "U$3") (pin "P$38") (pinfunction "P$38_P$38") (pintype "bidirectional"))
    )
    (net (code "151") (name "unconnected-(U$3-PadP$39)") (class "Default")
      (node (ref "U$3") (pin "P$39") (pinfunction "P$39_P$39") (pintype "bidirectional"))
    )
    (net (code "152") (name "unconnected-(U$3-PadP$40)") (class "Default")
      (node (ref "U$3") (pin "P$40") (pinfunction "P$40_P$40") (pintype "bidirectional"))
    )
    (net (code "153") (name "unconnected-(U$3-PadP$41)") (class "Default")
      (node (ref "U$3") (pin "P$41") (pinfunction "P$41_P$41") (pintype "bidirectional"))
    )
    (net (code "154") (name "unconnected-(U$3-PadP$42)") (class "Default")
      (node (ref "U$3") (pin "P$42") (pinfunction "P$42_P$42") (pintype "bidirectional"))
    )
    (net (code "155") (name "unconnected-(U$3-PadP$43)") (class "Default")
      (node (ref "U$3") (pin "P$43") (pinfunction "P$43_P$43") (pintype "bidirectional"))
    )
    (net (code "156") (name "unconnected-(U$3-PadP$44)") (class "Default")
      (node (ref "U$3") (pin "P$44") (pinfunction "P$44_P$44") (pintype "bidirectional"))
    )
    (net (code "157") (name "unconnected-(U$3-PadP$45)") (class "Default")
      (node (ref "U$3") (pin "P$45") (pinfunction "P$45_P$45") (pintype "bidirectional"))
    )
    (net (code "158") (name "unconnected-(U$3-PadP$46)") (class "Default")
      (node (ref "U$3") (pin "P$46") (pinfunction "P$46_P$46") (pintype "bidirectional"))
    )
    (net (code "159") (name "unconnected-(U$3-PadP$47)") (class "Default")
      (node (ref "U$3") (pin "P$47") (pinfunction "P$47_P$47") (pintype "bidirectional"))
    )
    (net (code "160") (name "unconnected-(U$3-PadP$48)") (class "Default")
      (node (ref "U$3") (pin "P$48") (pinfunction "P$48_P$48") (pintype "bidirectional"))
    )
    (net (code "161") (name "unconnected-(U$3-PadP$49)") (class "Default")
      (node (ref "U$3") (pin "P$49") (pinfunction "P$49_P$49") (pintype "bidirectional"))
    )
    (net (code "162") (name "unconnected-(U$3-PadP$50)") (class "Default")
      (node (ref "U$3") (pin "P$50") (pinfunction "P$50_P$50") (pintype "bidirectional"))
    )
    (net (code "163") (name "unconnected-(U$3-PadP$51)") (class "Default")
      (node (ref "U$3") (pin "P$51") (pinfunction "P$51_P$51") (pintype "bidirectional"))
    )
    (net (code "164") (name "unconnected-(U$3-PadP$52)") (class "Default")
      (node (ref "U$3") (pin "P$52") (pinfunction "P$52_P$52") (pintype "bidirectional"))
    )
    (net (code "165") (name "unconnected-(U$3-PadP$53)") (class "Default")
      (node (ref "U$3") (pin "P$53") (pinfunction "P$53_P$53") (pintype "bidirectional"))
    )
    (net (code "166") (name "unconnected-(U$3-PadP$54)") (class "Default")
      (node (ref "U$3") (pin "P$54") (pinfunction "P$54_P$54") (pintype "bidirectional"))
    )
    (net (code "167") (name "unconnected-(U$3-PadP$55)") (class "Default")
      (node (ref "U$3") (pin "P$55") (pinfunction "P$55_P$55") (pintype "bidirectional"))
    )
    (net (code "168") (name "unconnected-(U$3-PadP$56)") (class "Default")
      (node (ref "U$3") (pin "P$56") (pinfunction "P$56_P$56") (pintype "bidirectional"))
    )
    (net (code "169") (name "unconnected-(U$3-PadP$57)") (class "Default")
      (node (ref "U$3") (pin "P$57") (pinfunction "P$57_P$57") (pintype "bidirectional"))
    )
    (net (code "170") (name "unconnected-(U$3-PadP$58)") (class "Default")
      (node (ref "U$3") (pin "P$58") (pinfunction "P$58_P$58") (pintype "bidirectional"))
    )
    (net (code "171") (name "unconnected-(U$3-PadP$59)") (class "Default")
      (node (ref "U$3") (pin "P$59") (pinfunction "P$59_P$59") (pintype "bidirectional"))
    )
    (net (code "172") (name "unconnected-(U$3-PadP$60)") (class "Default")
      (node (ref "U$3") (pin "P$60") (pinfunction "P$60_P$60") (pintype "bidirectional"))
    )
    (net (code "173") (name "unconnected-(U$3-PadP$61)") (class "Default")
      (node (ref "U$3") (pin "P$61") (pinfunction "P$61_P$61") (pintype "bidirectional"))
    )
    (net (code "174") (name "unconnected-(U$3-PadP$62)") (class "Default")
      (node (ref "U$3") (pin "P$62") (pinfunction "P$62_P$62") (pintype "bidirectional"))
    )
    (net (code "175") (name "unconnected-(U$3-PadP$63)") (class "Default")
      (node (ref "U$3") (pin "P$63") (pinfunction "P$63_P$63") (pintype "bidirectional"))
    )
    (net (code "176") (name "unconnected-(U$3-PadP$64)") (class "Default")
      (node (ref "U$3") (pin "P$64") (pinfunction "P$64_P$64") (pintype "bidirectional"))
    )
    (net (code "177") (name "unconnected-(U$3-PadP$65)") (class "Default")
      (node (ref "U$3") (pin "P$65") (pinfunction "P$65_P$65") (pintype "bidirectional"))
    )
    (net (code "178") (name "unconnected-(U$3-PadP$66)") (class "Default")
      (node (ref "U$3") (pin "P$66") (pinfunction "P$66_P$66") (pintype "bidirectional"))
    )
    (net (code "179") (name "unconnected-(U$3-PadP$67)") (class "Default")
      (node (ref "U$3") (pin "P$67") (pinfunction "P$67_P$67") (pintype "bidirectional"))
    )
    (net (code "180") (name "unconnected-(U$3-PadP$68)") (class "Default")
      (node (ref "U$3") (pin "P$68") (pinfunction "P$68_P$68") (pintype "bidirectional"))
    )
    (net (code "181") (name "unconnected-(U$3-PadP$69)") (class "Default")
      (node (ref "U$3") (pin "P$69") (pinfunction "P$69_P$69") (pintype "bidirectional"))
    )
    (net (code "182") (name "unconnected-(U$3-PadP$70)") (class "Default")
      (node (ref "U$3") (pin "P$70") (pinfunction "P$70_P$70") (pintype "bidirectional"))
    )
    (net (code "183") (name "unconnected-(U$3-PadP$71)") (class "Default")
      (node (ref "U$3") (pin "P$71") (pinfunction "P$71_P$71") (pintype "bidirectional"))
    )
    (net (code "184") (name "unconnected-(U$3-PadP$72)") (class "Default")
      (node (ref "U$3") (pin "P$72") (pinfunction "P$72_P$72") (pintype "bidirectional"))
    )
    (net (code "185") (name "unconnected-(U$3-PadP$73)") (class "Default")
      (node (ref "U$3") (pin "P$73") (pinfunction "P$73_P$73") (pintype "bidirectional"))
    )
    (net (code "186") (name "unconnected-(U$3-PadP$74)") (class "Default")
      (node (ref "U$3") (pin "P$74") (pinfunction "P$74_P$74") (pintype "bidirectional"))
    )
    (net (code "187") (name "unconnected-(U$3-PadP$75)") (class "Default")
      (node (ref "U$3") (pin "P$75") (pinfunction "P$75_P$75") (pintype "bidirectional"))
    )
    (net (code "188") (name "unconnected-(U$3-PadP$76)") (class "Default")
      (node (ref "U$3") (pin "P$76") (pinfunction "P$76_P$76") (pintype "bidirectional"))
    )
    (net (code "189") (name "unconnected-(U$3-PadP$77)") (class "Default")
      (node (ref "U$3") (pin "P$77") (pinfunction "P$77_P$77") (pintype "bidirectional"))
    )
    (net (code "190") (name "unconnected-(U$3-PadP$78)") (class "Default")
      (node (ref "U$3") (pin "P$78") (pinfunction "P$78_P$78") (pintype "bidirectional"))
    )
    (net (code "191") (name "unconnected-(U$3-PadP$79)") (class "Default")
      (node (ref "U$3") (pin "P$79") (pinfunction "P$79_P$79") (pintype "bidirectional"))
    )
    (net (code "192") (name "unconnected-(U$3-PadP$80)") (class "Default")
      (node (ref "U$3") (pin "P$80") (pinfunction "P$80_P$80") (pintype "bidirectional"))
    )
    (net (code "193") (name "unconnected-(U$3-PadP$81)") (class "Default")
      (node (ref "U$3") (pin "P$81") (pinfunction "P$81_P$81") (pintype "bidirectional"))
    )
    (net (code "194") (name "unconnected-(U$3-PadP$82)") (class "Default")
      (node (ref "U$3") (pin "P$82") (pinfunction "P$82_P$82") (pintype "bidirectional"))
    )
    (net (code "195") (name "unconnected-(U$3-PadP$83)") (class "Default")
      (node (ref "U$3") (pin "P$83") (pinfunction "P$83_P$83") (pintype "bidirectional"))
    )
    (net (code "196") (name "unconnected-(U$3-PadP$84)") (class "Default")
      (node (ref "U$3") (pin "P$84") (pinfunction "P$84_P$84") (pintype "bidirectional"))
    )
    (net (code "197") (name "unconnected-(U$3-PadP$85)") (class "Default")
      (node (ref "U$3") (pin "P$85") (pinfunction "P$85_P$85") (pintype "bidirectional"))
    )
    (net (code "198") (name "unconnected-(U$3-PadP$86)") (class "Default")
      (node (ref "U$3") (pin "P$86") (pinfunction "P$86_P$86") (pintype "bidirectional"))
    )
    (net (code "199") (name "unconnected-(U$3-PadP$87)") (class "Default")
      (node (ref "U$3") (pin "P$87") (pinfunction "P$87_P$87") (pintype "bidirectional"))
    )
    (net (code "200") (name "unconnected-(U$3-PadP$88)") (class "Default")
      (node (ref "U$3") (pin "P$88") (pinfunction "P$88_P$88") (pintype "bidirectional"))
    )
    (net (code "201") (name "unconnected-(U$3-PadP$89)") (class "Default")
      (node (ref "U$3") (pin "P$89") (pinfunction "P$89_P$89") (pintype "bidirectional"))
    )
    (net (code "202") (name "unconnected-(U$3-PadP$90)") (class "Default")
      (node (ref "U$3") (pin "P$90") (pinfunction "P$90_P$90") (pintype "bidirectional"))
    )
    (net (code "203") (name "unconnected-(U$3-PadP$91)") (class "Default")
      (node (ref "U$3") (pin "P$91") (pinfunction "P$91_P$91") (pintype "bidirectional"))
    )
    (net (code "204") (name "unconnected-(U$3-PadP$92)") (class "Default")
      (node (ref "U$3") (pin "P$92") (pinfunction "P$92_P$92") (pintype "bidirectional"))
    )
    (net (code "205") (name "unconnected-(U$3-PadP$93)") (class "Default")
      (node (ref "U$3") (pin "P$93") (pinfunction "P$93_P$93") (pintype "bidirectional"))
    )
    (net (code "206") (name "unconnected-(U$3-PadP$94)") (class "Default")
      (node (ref "U$3") (pin "P$94") (pinfunction "P$94_P$94") (pintype "bidirectional"))
    )
    (net (code "207") (name "unconnected-(U$3-PadP$95)") (class "Default")
      (node (ref "U$3") (pin "P$95") (pinfunction "P$95_P$95") (pintype "bidirectional"))
    )
    (net (code "208") (name "unconnected-(U$3-PadP$96)") (class "Default")
      (node (ref "U$3") (pin "P$96") (pinfunction "P$96_P$96") (pintype "bidirectional"))
    )
    (net (code "209") (name "unconnected-(U$3-PadP$97)") (class "Default")
      (node (ref "U$3") (pin "P$97") (pinfunction "P$97_P$97") (pintype "bidirectional"))
    )
    (net (code "210") (name "unconnected-(U$3-PadP$98)") (class "Default")
      (node (ref "U$3") (pin "P$98") (pinfunction "P$98_P$98") (pintype "bidirectional"))
    )
    (net (code "211") (name "unconnected-(U$3-PadP$99)") (class "Default")
      (node (ref "U$3") (pin "P$99") (pinfunction "P$99_P$99") (pintype "bidirectional"))
    )
    (net (code "212") (name "unconnected-(U$3-PadP$100)") (class "Default")
      (node (ref "U$3") (pin "P$100") (pinfunction "P$100_P$100") (pintype "bidirectional"))
    )
    (net (code "213") (name "unconnected-(U$3-PadP$101)") (class "Default")
      (node (ref "U$3") (pin "P$101") (pinfunction "P$101_P$101") (pintype "bidirectional"))
    )
    (net (code "214") (name "unconnected-(U$3-PadP$102)") (class "Default")
      (node (ref "U$3") (pin "P$102") (pinfunction "P$102_P$102") (pintype "bidirectional"))
    )
    (net (code "215") (name "unconnected-(U$3-PadP$103)") (class "Default")
      (node (ref "U$3") (pin "P$103") (pinfunction "P$103_P$103") (pintype "bidirectional"))
    )
    (net (code "216") (name "unconnected-(U$3-PadP$104)") (class "Default")
      (node (ref "U$3") (pin "P$104") (pinfunction "P$104_P$104") (pintype "bidirectional"))
    )
    (net (code "217") (name "unconnected-(U$3-PadP$105)") (class "Default")
      (node (ref "U$3") (pin "P$105") (pinfunction "P$105_P$105") (pintype "bidirectional"))
    )
    (net (code "218") (name "unconnected-(U$3-PadP$106)") (class "Default")
      (node (ref "U$3") (pin "P$106") (pinfunction "P$106_P$106") (pintype "bidirectional"))
    )
    (net (code "219") (name "unconnected-(U$3-PadP$107)") (class "Default")
      (node (ref "U$3") (pin "P$107") (pinfunction "P$107_P$107") (pintype "bidirectional"))
    )
    (net (code "220") (name "unconnected-(U$3-PadP$108)") (class "Default")
      (node (ref "U$3") (pin "P$108") (pinfunction "P$108_P$108") (pintype "bidirectional"))
    )
    (net (code "221") (name "unconnected-(U$3-PadP$109)") (class "Default")
      (node (ref "U$3") (pin "P$109") (pinfunction "P$109_P$109") (pintype "bidirectional"))
    )
    (net (code "222") (name "unconnected-(U$3-PadP$110)") (class "Default")
      (node (ref "U$3") (pin "P$110") (pinfunction "P$110_P$110") (pintype "bidirectional"))
    )
    (net (code "223") (name "unconnected-(U$3-PadP$111)") (class "Default")
      (node (ref "U$3") (pin "P$111") (pinfunction "P$111_P$111") (pintype "bidirectional"))
    )
    (net (code "224") (name "unconnected-(U$3-PadP$112)") (class "Default")
      (node (ref "U$3") (pin "P$112") (pinfunction "P$112_P$112") (pintype "bidirectional"))
    )
    (net (code "225") (name "unconnected-(U$3-PadP$113)") (class "Default")
      (node (ref "U$3") (pin "P$113") (pinfunction "P$113_P$113") (pintype "bidirectional"))
    )
    (net (code "226") (name "unconnected-(U$3-PadP$114)") (class "Default")
      (node (ref "U$3") (pin "P$114") (pinfunction "P$114_P$114") (pintype "bidirectional"))
    )
    (net (code "227") (name "unconnected-(U$3-PadP$115)") (class "Default")
      (node (ref "U$3") (pin "P$115") (pinfunction "P$115_P$115") (pintype "bidirectional"))
    )
    (net (code "228") (name "unconnected-(U$3-PadP$116)") (class "Default")
      (node (ref "U$3") (pin "P$116") (pinfunction "P$116_P$116") (pintype "bidirectional"))
    )
    (net (code "229") (name "unconnected-(U$3-PadP$117)") (class "Default")
      (node (ref "U$3") (pin "P$117") (pinfunction "P$117_P$117") (pintype "bidirectional"))
    )
    (net (code "230") (name "unconnected-(U$3-PadP$118)") (class "Default")
      (node (ref "U$3") (pin "P$118") (pinfunction "P$118_P$118") (pintype "bidirectional"))
    )
    (net (code "231") (name "unconnected-(U$3-PadP$119)") (class "Default")
      (node (ref "U$3") (pin "P$119") (pinfunction "P$119_P$119") (pintype "bidirectional"))
    )
    (net (code "232") (name "unconnected-(U$3-PadP$120)") (class "Default")
      (node (ref "U$3") (pin "P$120") (pinfunction "P$120_P$120") (pintype "bidirectional"))
    )
    (net (code "233") (name "unconnected-(U$3-PadP$121)") (class "Default")
      (node (ref "U$3") (pin "P$121") (pinfunction "P$121_P$121") (pintype "bidirectional"))
    )
    (net (code "234") (name "unconnected-(U$3-PadP$122)") (class "Default")
      (node (ref "U$3") (pin "P$122") (pinfunction "P$122_P$122") (pintype "bidirectional"))
    )
    (net (code "235") (name "unconnected-(U$3-PadP$123)") (class "Default")
      (node (ref "U$3") (pin "P$123") (pinfunction "P$123_P$123") (pintype "bidirectional"))
    )
    (net (code "236") (name "unconnected-(U$3-PadP$124)") (class "Default")
      (node (ref "U$3") (pin "P$124") (pinfunction "P$124_P$124") (pintype "bidirectional"))
    )
    (net (code "237") (name "unconnected-(U$3-PadP$125)") (class "Default")
      (node (ref "U$3") (pin "P$125") (pinfunction "P$125_P$125") (pintype "bidirectional"))
    )
    (net (code "238") (name "unconnected-(U$3-PadP$126)") (class "Default")
      (node (ref "U$3") (pin "P$126") (pinfunction "P$126_P$126") (pintype "bidirectional"))
    )
    (net (code "239") (name "unconnected-(U$3-PadP$127)") (class "Default")
      (node (ref "U$3") (pin "P$127") (pinfunction "P$127_P$127") (pintype "bidirectional"))
    )
    (net (code "240") (name "unconnected-(U$3-PadP$128)") (class "Default")
      (node (ref "U$3") (pin "P$128") (pinfunction "P$128_P$128") (pintype "bidirectional"))
    )
    (net (code "241") (name "unconnected-(U$3-PadP$129)") (class "Default")
      (node (ref "U$3") (pin "P$129") (pinfunction "P$129_P$129") (pintype "bidirectional"))
    )
    (net (code "242") (name "unconnected-(U$3-PadP$130)") (class "Default")
      (node (ref "U$3") (pin "P$130") (pinfunction "P$130_P$130") (pintype "bidirectional"))
    )
    (net (code "243") (name "unconnected-(U$3-PadP$131)") (class "Default")
      (node (ref "U$3") (pin "P$131") (pinfunction "P$131_P$131") (pintype "bidirectional"))
    )
    (net (code "244") (name "unconnected-(U$3-PadP$132)") (class "Default")
      (node (ref "U$3") (pin "P$132") (pinfunction "P$132_P$132") (pintype "bidirectional"))
    )
    (net (code "245") (name "unconnected-(U$3-PadP$133)") (class "Default")
      (node (ref "U$3") (pin "P$133") (pinfunction "P$133_P$133") (pintype "bidirectional"))
    )
    (net (code "246") (name "unconnected-(U$3-PadP$134)") (class "Default")
      (node (ref "U$3") (pin "P$134") (pinfunction "P$134_P$134") (pintype "bidirectional"))
    )
    (net (code "247") (name "unconnected-(U$3-PadP$135)") (class "Default")
      (node (ref "U$3") (pin "P$135") (pinfunction "P$135_P$135") (pintype "bidirectional"))
    )
    (net (code "248") (name "unconnected-(U$3-PadP$136)") (class "Default")
      (node (ref "U$3") (pin "P$136") (pinfunction "P$136_P$136") (pintype "bidirectional"))
    )
    (net (code "249") (name "unconnected-(U$3-PadP$137)") (class "Default")
      (node (ref "U$3") (pin "P$137") (pinfunction "P$137_P$137") (pintype "bidirectional"))
    )
    (net (code "250") (name "unconnected-(U$3-PadP$138)") (class "Default")
      (node (ref "U$3") (pin "P$138") (pinfunction "P$138_P$138") (pintype "bidirectional"))
    )
    (net (code "251") (name "unconnected-(U$3-PadP$139)") (class "Default")
      (node (ref "U$3") (pin "P$139") (pinfunction "P$139_P$139") (pintype "bidirectional"))
    )
    (net (code "252") (name "unconnected-(U$3-PadP$140)") (class "Default")
      (node (ref "U$3") (pin "P$140") (pinfunction "P$140_P$140") (pintype "bidirectional"))
    )
    (net (code "253") (name "unconnected-(U$3-PadP$141)") (class "Default")
      (node (ref "U$3") (pin "P$141") (pinfunction "P$141_P$141") (pintype "bidirectional"))
    )
    (net (code "254") (name "unconnected-(U$3-PadP$142)") (class "Default")
      (node (ref "U$3") (pin "P$142") (pinfunction "P$142_P$142") (pintype "bidirectional"))
    )
    (net (code "255") (name "unconnected-(U$3-PadP$143)") (class "Default")
      (node (ref "U$3") (pin "P$143") (pinfunction "P$143_P$143") (pintype "bidirectional"))
    )
    (net (code "256") (name "unconnected-(U$3-PadP$144)") (class "Default")
      (node (ref "U$3") (pin "P$144") (pinfunction "P$144_P$144") (pintype "bidirectional"))
    )
    (net (code "257") (name "unconnected-(U$3-PadP$145)") (class "Default")
      (node (ref "U$3") (pin "P$145") (pinfunction "P$145_P$145") (pintype "bidirectional"))
    )
    (net (code "258") (name "unconnected-(U$3-PadP$146)") (class "Default")
      (node (ref "U$3") (pin "P$146") (pinfunction "P$146_P$146") (pintype "bidirectional"))
    )
    (net (code "259") (name "unconnected-(U$3-PadP$147)") (class "Default")
      (node (ref "U$3") (pin "P$147") (pinfunction "P$147_P$147") (pintype "bidirectional"))
    )
    (net (code "260") (name "unconnected-(U$3-PadP$148)") (class "Default")
      (node (ref "U$3") (pin "P$148") (pinfunction "P$148_P$148") (pintype "bidirectional"))
    )
    (net (code "261") (name "unconnected-(U$3-PadP$149)") (class "Default")
      (node (ref "U$3") (pin "P$149") (pinfunction "P$149_P$149") (pintype "bidirectional"))
    )
    (net (code "262") (name "unconnected-(U$3-PadP$150)") (class "Default")
      (node (ref "U$3") (pin "P$150") (pinfunction "P$150_P$150") (pintype "bidirectional"))
    )
    (net (code "263") (name "unconnected-(U$3-PadP$151)") (class "Default")
      (node (ref "U$3") (pin "P$151") (pinfunction "P$151_P$151") (pintype "bidirectional"))
    )
    (net (code "264") (name "unconnected-(U$3-PadP$152)") (class "Default")
      (node (ref "U$3") (pin "P$152") (pinfunction "P$152_P$152") (pintype "bidirectional"))
    )
    (net (code "265") (name "unconnected-(U$3-PadP$153)") (class "Default")
      (node (ref "U$3") (pin "P$153") (pinfunction "P$153_P$153") (pintype "bidirectional"))
    )
    (net (code "266") (name "unconnected-(U$3-PadP$154)") (class "Default")
      (node (ref "U$3") (pin "P$154") (pinfunction "P$154_P$154") (pintype "bidirectional"))
    )
    (net (code "267") (name "unconnected-(U$3-PadP$155)") (class "Default")
      (node (ref "U$3") (pin "P$155") (pinfunction "P$155_P$155") (pintype "bidirectional"))
    )
    (net (code "268") (name "unconnected-(U$3-PadP$156)") (class "Default")
      (node (ref "U$3") (pin "P$156") (pinfunction "P$156_P$156") (pintype "bidirectional"))
    )
    (net (code "269") (name "unconnected-(U$3-PadP$157)") (class "Default")
      (node (ref "U$3") (pin "P$157") (pinfunction "P$157_P$157") (pintype "bidirectional"))
    )
    (net (code "270") (name "unconnected-(U$3-PadP$158)") (class "Default")
      (node (ref "U$3") (pin "P$158") (pinfunction "P$158_P$158") (pintype "bidirectional"))
    )
    (net (code "271") (name "unconnected-(U$3-PadP$159)") (class "Default")
      (node (ref "U$3") (pin "P$159") (pinfunction "P$159_P$159") (pintype "bidirectional"))
    )
    (net (code "272") (name "unconnected-(U$3-PadP$160)") (class "Default")
      (node (ref "U$3") (pin "P$160") (pinfunction "P$160_P$160") (pintype "bidirectional"))
    )
    (net (code "273") (name "unconnected-(U$26-4-PadP$4)") (class "Default")
      (node (ref "U$26") (pin "P$4") (pinfunction "4_P$4") (pintype "bidirectional"))
    )
    (net (code "274") (name "unconnected-(U$27-4-PadP$4)") (class "Default")
      (node (ref "U$27") (pin "P$4") (pinfunction "4_P$4") (pintype "bidirectional"))
    )
    (net (code "275") (name "unconnected-(U$28-4-PadP$4)") (class "Default")
      (node (ref "U$28") (pin "P$4") (pinfunction "4_P$4") (pintype "bidirectional"))
    )
    (net (code "276") (name "unconnected-(U$29-1-PadP$1)") (class "Default")
      (node (ref "U$29") (pin "P$1") (pinfunction "1_P$1") (pintype "bidirectional"))
    )
    (net (code "277") (name "unconnected-(U$29-2-PadP$2)") (class "Default")
      (node (ref "U$29") (pin "P$2") (pinfunction "2_P$2") (pintype "bidirectional"))
    )
    (net (code "278") (name "unconnected-(U$30-1-PadP$1)") (class "Default")
      (node (ref "U$30") (pin "P$1") (pinfunction "1_P$1") (pintype "bidirectional"))
    )
    (net (code "279") (name "unconnected-(U$30-2-PadP$2)") (class "Default")
      (node (ref "U$30") (pin "P$2") (pinfunction "2_P$2") (pintype "bidirectional"))
    )
    (net (code "280") (name "unconnected-(U$31-1-PadP$1)") (class "Default")
      (node (ref "U$31") (pin "P$1") (pinfunction "1_P$1") (pintype "bidirectional"))
    )
    (net (code "281") (name "unconnected-(U$31-2-PadP$2)") (class "Default")
      (node (ref "U$31") (pin "P$2") (pinfunction "2_P$2") (pintype "bidirectional"))
    )
    (net (code "282") (name "unconnected-(U$33-1-PadP$1)") (class "Default")
      (node (ref "U$33") (pin "P$1") (pinfunction "1_P$1") (pintype "bidirectional"))
    )
    (net (code "283") (name "unconnected-(U$33-2-PadP$2)") (class "Default")
      (node (ref "U$33") (pin "P$2") (pinfunction "2_P$2") (pintype "bidirectional"))
    )
    (net (code "284") (name "unconnected-(U$33-3-PadP$3)") (class "Default")
      (node (ref "U$33") (pin "P$3") (pinfunction "3_P$3") (pintype "bidirectional"))
    )
    (net (code "285") (name "unconnected-(U$33-4-PadP$4)") (class "Default")
      (node (ref "U$33") (pin "P$4") (pinfunction "4_P$4") (pintype "bidirectional"))
    )
    (net (code "286") (name "unconnected-(U$33-5-PadP$5)") (class "Default")
      (node (ref "U$33") (pin "P$5") (pinfunction "5_P$5") (pintype "bidirectional"))
    )
    (net (code "287") (name "unconnected-(U$33-6-PadP$6)") (class "Default")
      (node (ref "U$33") (pin "P$6") (pinfunction "6_P$6") (pintype "bidirectional"))
    )
    (net (code "288") (name "unconnected-(U$34-1-PadP$4)") (class "Default")
      (node (ref "U$34") (pin "P$4") (pinfunction "1_P$4") (pintype "bidirectional"))
    )
    (net (code "289") (name "unconnected-(U$34-2-PadP$3)") (class "Default")
      (node (ref "U$34") (pin "P$3") (pinfunction "2_P$3") (pintype "bidirectional"))
    )
    (net (code "290") (name "unconnected-(U$34-3-PadP$2)") (class "Default")
      (node (ref "U$34") (pin "P$2") (pinfunction "3_P$2") (pintype "bidirectional"))
    )
    (net (code "291") (name "unconnected-(U$34-4-PadP$1)") (class "Default")
      (node (ref "U$34") (pin "P$1") (pinfunction "4_P$1") (pintype "bidirectional"))
    )
    (net (code "292") (name "unconnected-(U$35-1-PadP$4)") (class "Default")
      (node (ref "U$35") (pin "P$4") (pinfunction "1_P$4") (pintype "bidirectional"))
    )
    (net (code "293") (name "unconnected-(U$35-2-PadP$3)") (class "Default")
      (node (ref "U$35") (pin "P$3") (pinfunction "2_P$3") (pintype "bidirectional"))
    )
    (net (code "294") (name "unconnected-(U$35-3-PadP$2)") (class "Default")
      (node (ref "U$35") (pin "P$2") (pinfunction "3_P$2") (pintype "bidirectional"))
    )
    (net (code "295") (name "unconnected-(U$35-4-PadP$1)") (class "Default")
      (node (ref "U$35") (pin "P$1") (pinfunction "4_P$1") (pintype "bidirectional"))
    )
    (net (code "296") (name "unconnected-(U$36-1-PadP$4)") (class "Default")
      (node (ref "U$36") (pin "P$4") (pinfunction "1_P$4") (pintype "bidirectional"))
    )
    (net (code "297") (name "unconnected-(U$36-2-PadP$3)") (class "Default")
      (node (ref "U$36") (pin "P$3") (pinfunction "2_P$3") (pintype "bidirectional"))
    )
    (net (code "298") (name "unconnected-(U$36-3-PadP$2)") (class "Default")
      (node (ref "U$36") (pin "P$2") (pinfunction "3_P$2") (pintype "bidirectional"))
    )
    (net (code "299") (name "unconnected-(U$36-4-PadP$1)") (class "Default")
      (node (ref "U$36") (pin "P$1") (pinfunction "4_P$1") (pintype "bidirectional"))
    )
    (net (code "300") (name "unconnected-(U$37-1-PadP$1)") (class "Default")
      (node (ref "U$37") (pin "P$1") (pinfunction "1_P$1") (pintype "bidirectional"))
    )
    (net (code "301") (name "unconnected-(U$37-2-PadP$2)") (class "Default")
      (node (ref "U$37") (pin "P$2") (pinfunction "2_P$2") (pintype "bidirectional"))
    )
    (net (code "302") (name "unconnected-(U$37-3-PadP$3)") (class "Default")
      (node (ref "U$37") (pin "P$3") (pinfunction "3_P$3") (pintype "bidirectional"))
    )
    (net (code "303") (name "unconnected-(U$38-1-PadP$1)") (class "Default")
      (node (ref "U$38") (pin "P$1") (pinfunction "1_P$1") (pintype "bidirectional"))
    )
    (net (code "304") (name "unconnected-(U$38-2-PadP$2)") (class "Default")
      (node (ref "U$38") (pin "P$2") (pinfunction "2_P$2") (pintype "bidirectional"))
    )
    (net (code "305") (name "unconnected-(U$38-3-PadP$3)") (class "Default")
      (node (ref "U$38") (pin "P$3") (pinfunction "3_P$3") (pintype "bidirectional"))
    )
    (net (code "306") (name "unconnected-(U$39-1-PadP$1)") (class "Default")
      (node (ref "U$39") (pin "P$1") (pinfunction "1_P$1") (pintype "bidirectional"))
    )
    (net (code "307") (name "unconnected-(U$39-2-PadP$2)") (class "Default")
      (node (ref "U$39") (pin "P$2") (pinfunction "2_P$2") (pintype "bidirectional"))
    )
    (net (code "308") (name "unconnected-(U$39-3-PadP$3)") (class "Default")
      (node (ref "U$39") (pin "P$3") (pinfunction "3_P$3") (pintype "bidirectional"))
    )
    (net (code "309") (name "unconnected-(U$40-1-PadP$1)") (class "Default")
      (node (ref "U$40") (pin "P$1") (pinfunction "1_P$1") (pintype "bidirectional"))
    )
    (net (code "310") (name "unconnected-(U$40-2-PadP$2)") (class "Default")
      (node (ref "U$40") (pin "P$2") (pinfunction "2_P$2") (pintype "bidirectional"))
    )
    (net (code "311") (name "unconnected-(U$40-3-PadP$3)") (class "Default")
      (node (ref "U$40") (pin "P$3") (pinfunction "3_P$3") (pintype "bidirectional"))
    )
    (net (code "312") (name "unconnected-(U$41-1-PadP$1)") (class "Default")
      (node (ref "U$41") (pin "P$1") (pinfunction "1_P$1") (pintype "bidirectional"))
    )
    (net (code "313") (name "unconnected-(U$41-2-PadP$2)") (class "Default")
      (node (ref "U$41") (pin "P$2") (pinfunction "2_P$2") (pintype "bidirectional"))
    )
    (net (code "314") (name "unconnected-(U$41-3-PadP$3)") (class "Default")
      (node (ref "U$41") (pin "P$3") (pinfunction "3_P$3") (pintype "bidirectional"))
    )
    (net (code "315") (name "unconnected-(U$42-1-PadP$1)") (class "Default")
      (node (ref "U$42") (pin "P$1") (pinfunction "1_P$1") (pintype "bidirectional"))
    )
    (net (code "316") (name "unconnected-(U$42-2-PadP$2)") (class "Default")
      (node (ref "U$42") (pin "P$2") (pinfunction "2_P$2") (pintype "bidirectional"))
    )
    (net (code "317") (name "unconnected-(U$42-3-PadP$3)") (class "Default")
      (node (ref "U$42") (pin "P$3") (pinfunction "3_P$3") (pintype "bidirectional"))
    )
    (net (code "318") (name "unconnected-(U$43-1-PadP$1)") (class "Default")
      (node (ref "U$43") (pin "P$1") (pinfunction "1_P$1") (pintype "bidirectional"))
    )
    (net (code "319") (name "unconnected-(U$43-2-PadP$2)") (class "Default")
      (node (ref "U$43") (pin "P$2") (pinfunction "2_P$2") (pintype "bidirectional"))
    )
    (net (code "320") (name "unconnected-(U$43-3-PadP$3)") (class "Default")
      (node (ref "U$43") (pin "P$3") (pinfunction "3_P$3") (pintype "bidirectional"))
    )
    (net (code "321") (name "unconnected-(U$44-1-PadP$1)") (class "Default")
      (node (ref "U$44") (pin "P$1") (pinfunction "1_P$1") (pintype "bidirectional"))
    )
    (net (code "322") (name "unconnected-(U$44-2-PadP$2)") (class "Default")
      (node (ref "U$44") (pin "P$2") (pinfunction "2_P$2") (pintype "bidirectional"))
    )
    (net (code "323") (name "unconnected-(U$44-3-PadP$3)") (class "Default")
      (node (ref "U$44") (pin "P$3") (pinfunction "3_P$3") (pintype "bidirectional"))
    )
    (net (code "324") (name "unconnected-(U$45-1-PadP$1)") (class "Default")
      (node (ref "U$45") (pin "P$1") (pinfunction "1_P$1") (pintype "bidirectional"))
    )
    (net (code "325") (name "unconnected-(U$45-2-PadP$2)") (class "Default")
      (node (ref "U$45") (pin "P$2") (pinfunction "2_P$2") (pintype "bidirectional"))
    )
    (net (code "326") (name "unconnected-(U$45-3-PadP$3)") (class "Default")
      (node (ref "U$45") (pin "P$3") (pinfunction "3_P$3") (pintype "bidirectional"))
    )
    (net (code "327") (name "unconnected-(U$46-1-PadP$1)") (class "Default")
      (node (ref "U$46") (pin "P$1") (pinfunction "1_P$1") (pintype "bidirectional"))
    )
    (net (code "328") (name "unconnected-(U$46-2-PadP$2)") (class "Default")
      (node (ref "U$46") (pin "P$2") (pinfunction "2_P$2") (pintype "bidirectional"))
    )
    (net (code "329") (name "unconnected-(U$46-3-PadP$3)") (class "Default")
      (node (ref "U$46") (pin "P$3") (pinfunction "3_P$3") (pintype "bidirectional"))
    )
    (net (code "330") (name "unconnected-(U$47-1-PadP$1)") (class "Default")
      (node (ref "U$47") (pin "P$1") (pinfunction "1_P$1") (pintype "bidirectional"))
    )
    (net (code "331") (name "unconnected-(U$47-2-PadP$2)") (class "Default")
      (node (ref "U$47") (pin "P$2") (pinfunction "2_P$2") (pintype "bidirectional"))
    )
    (net (code "332") (name "unconnected-(U$47-3-PadP$3)") (class "Default")
      (node (ref "U$47") (pin "P$3") (pinfunction "3_P$3") (pintype "bidirectional"))
    )
    (net (code "333") (name "unconnected-(U$48-1-PadP$1)") (class "Default")
      (node (ref "U$48") (pin "P$1") (pinfunction "1_P$1") (pintype "bidirectional"))
    )
    (net (code "334") (name "unconnected-(U$48-2-PadP$2)") (class "Default")
      (node (ref "U$48") (pin "P$2") (pinfunction "2_P$2") (pintype "bidirectional"))
    )
    (net (code "335") (name "unconnected-(U$48-3-PadP$3)") (class "Default")
      (node (ref "U$48") (pin "P$3") (pinfunction "3_P$3") (pintype "bidirectional"))
    )
    (net (code "336") (name "unconnected-(U$49-1-PadP$1)") (class "Default")
      (node (ref "U$49") (pin "P$1") (pinfunction "1_P$1") (pintype "bidirectional"))
    )
    (net (code "337") (name "unconnected-(U$49-2-PadP$2)") (class "Default")
      (node (ref "U$49") (pin "P$2") (pinfunction "2_P$2") (pintype "bidirectional"))
    )
    (net (code "338") (name "unconnected-(U$49-3-PadP$3)") (class "Default")
      (node (ref "U$49") (pin "P$3") (pinfunction "3_P$3") (pintype "bidirectional"))
    )
    (net (code "339") (name "unconnected-(U$50-1-PadP$1)") (class "Default")
      (node (ref "U$50") (pin "P$1") (pinfunction "1_P$1") (pintype "bidirectional"))
    )
    (net (code "340") (name "unconnected-(U$50-2-PadP$2)") (class "Default")
      (node (ref "U$50") (pin "P$2") (pinfunction "2_P$2") (pintype "bidirectional"))
    )
    (net (code "341") (name "unconnected-(U$50-3-PadP$3)") (class "Default")
      (node (ref "U$50") (pin "P$3") (pinfunction "3_P$3") (pintype "bidirectional"))
    )
  )
)
